# FPGA_MGT.net
KiCad netlist of a schematic drawn in Altium Designer
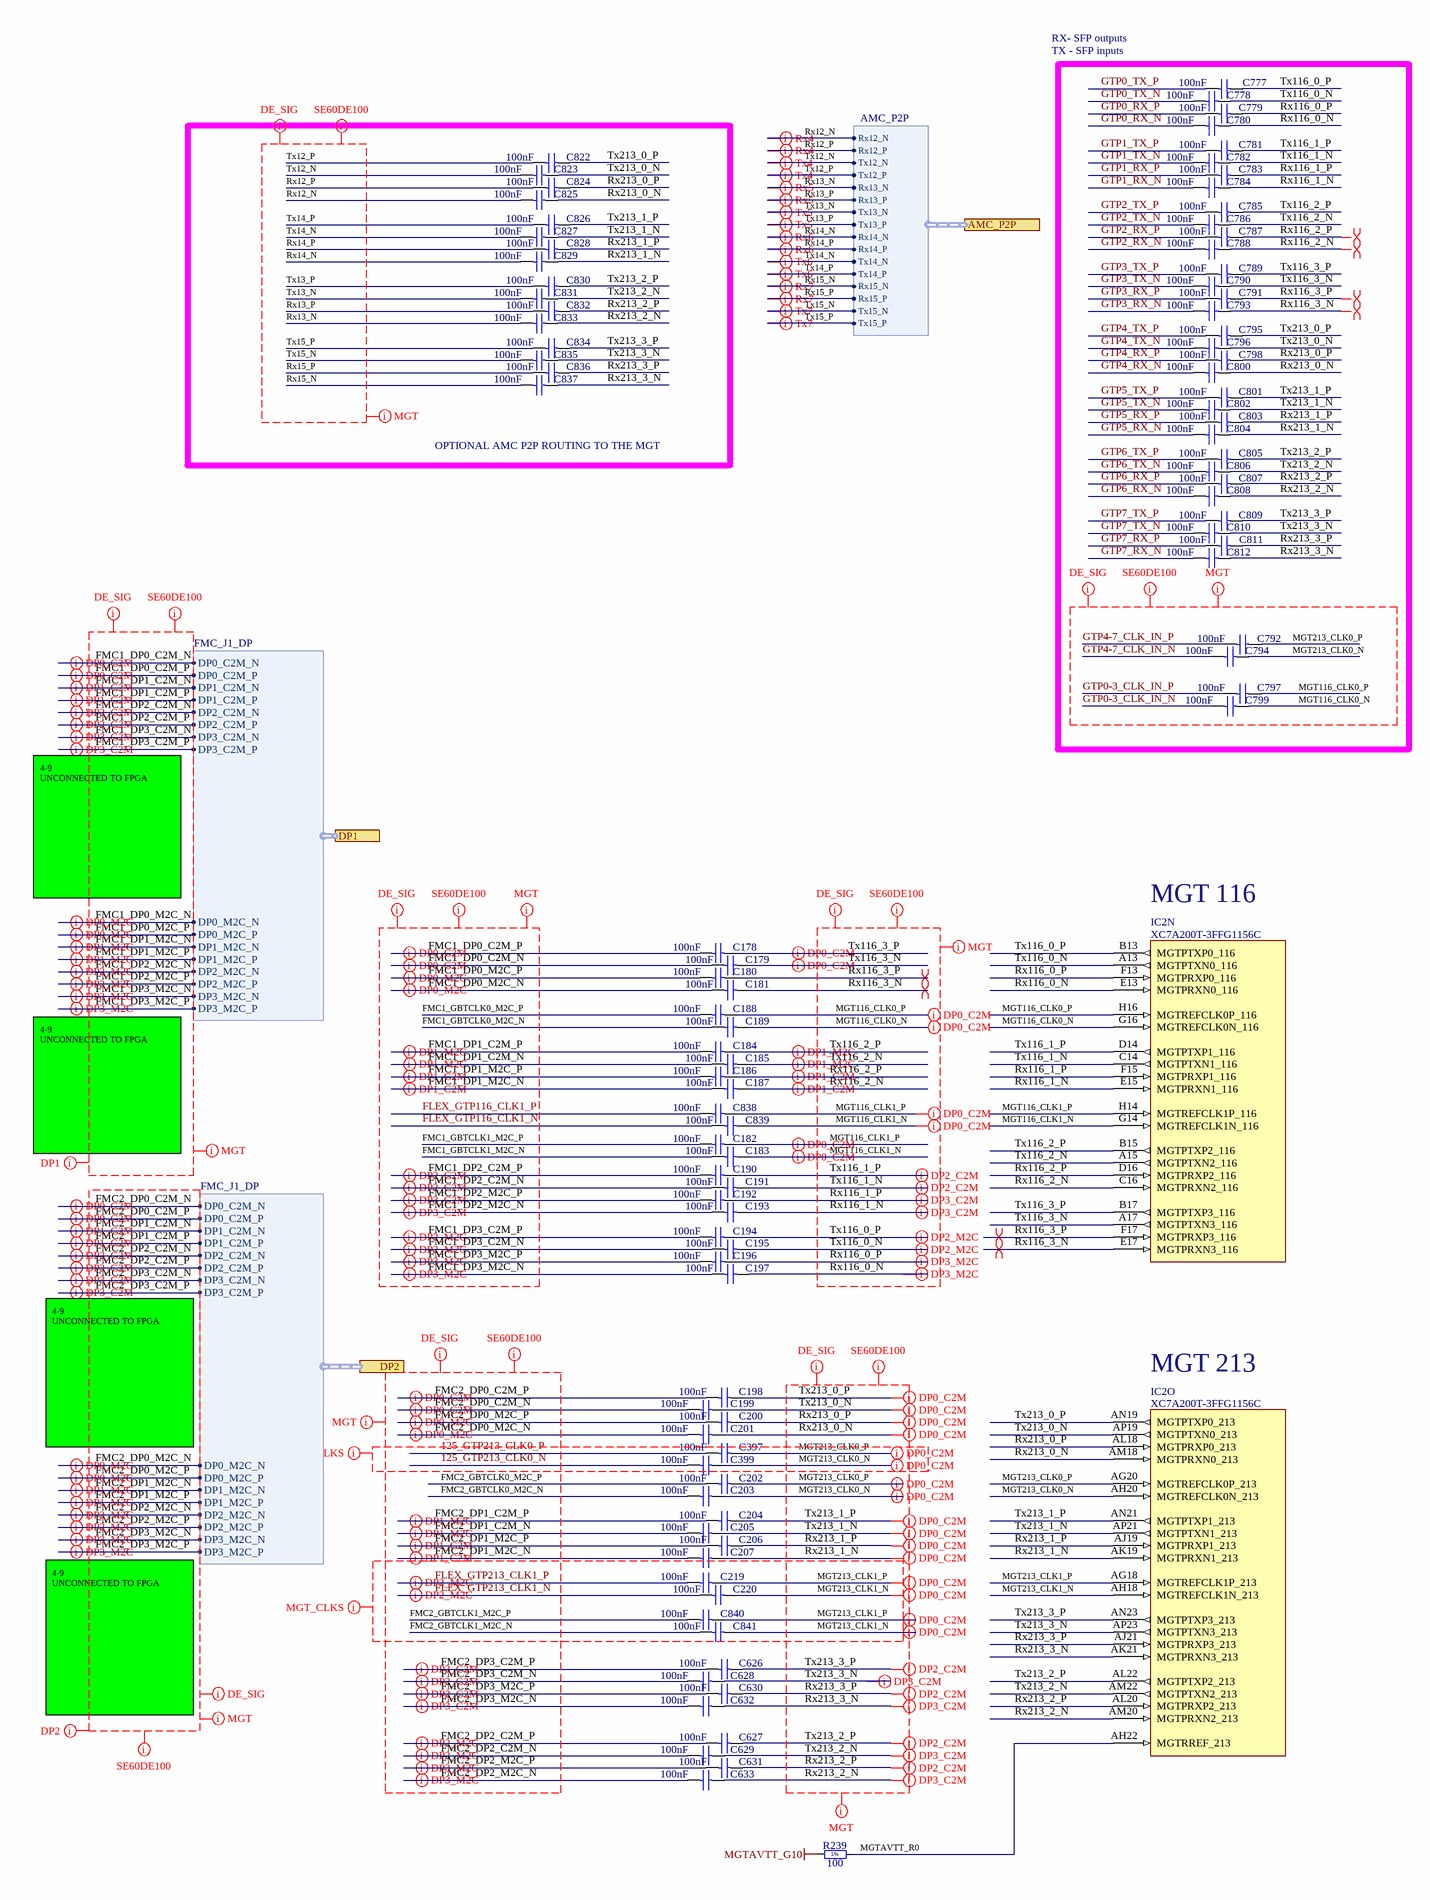
[diagram p0: FPGA_MGT.SchDoc, left]
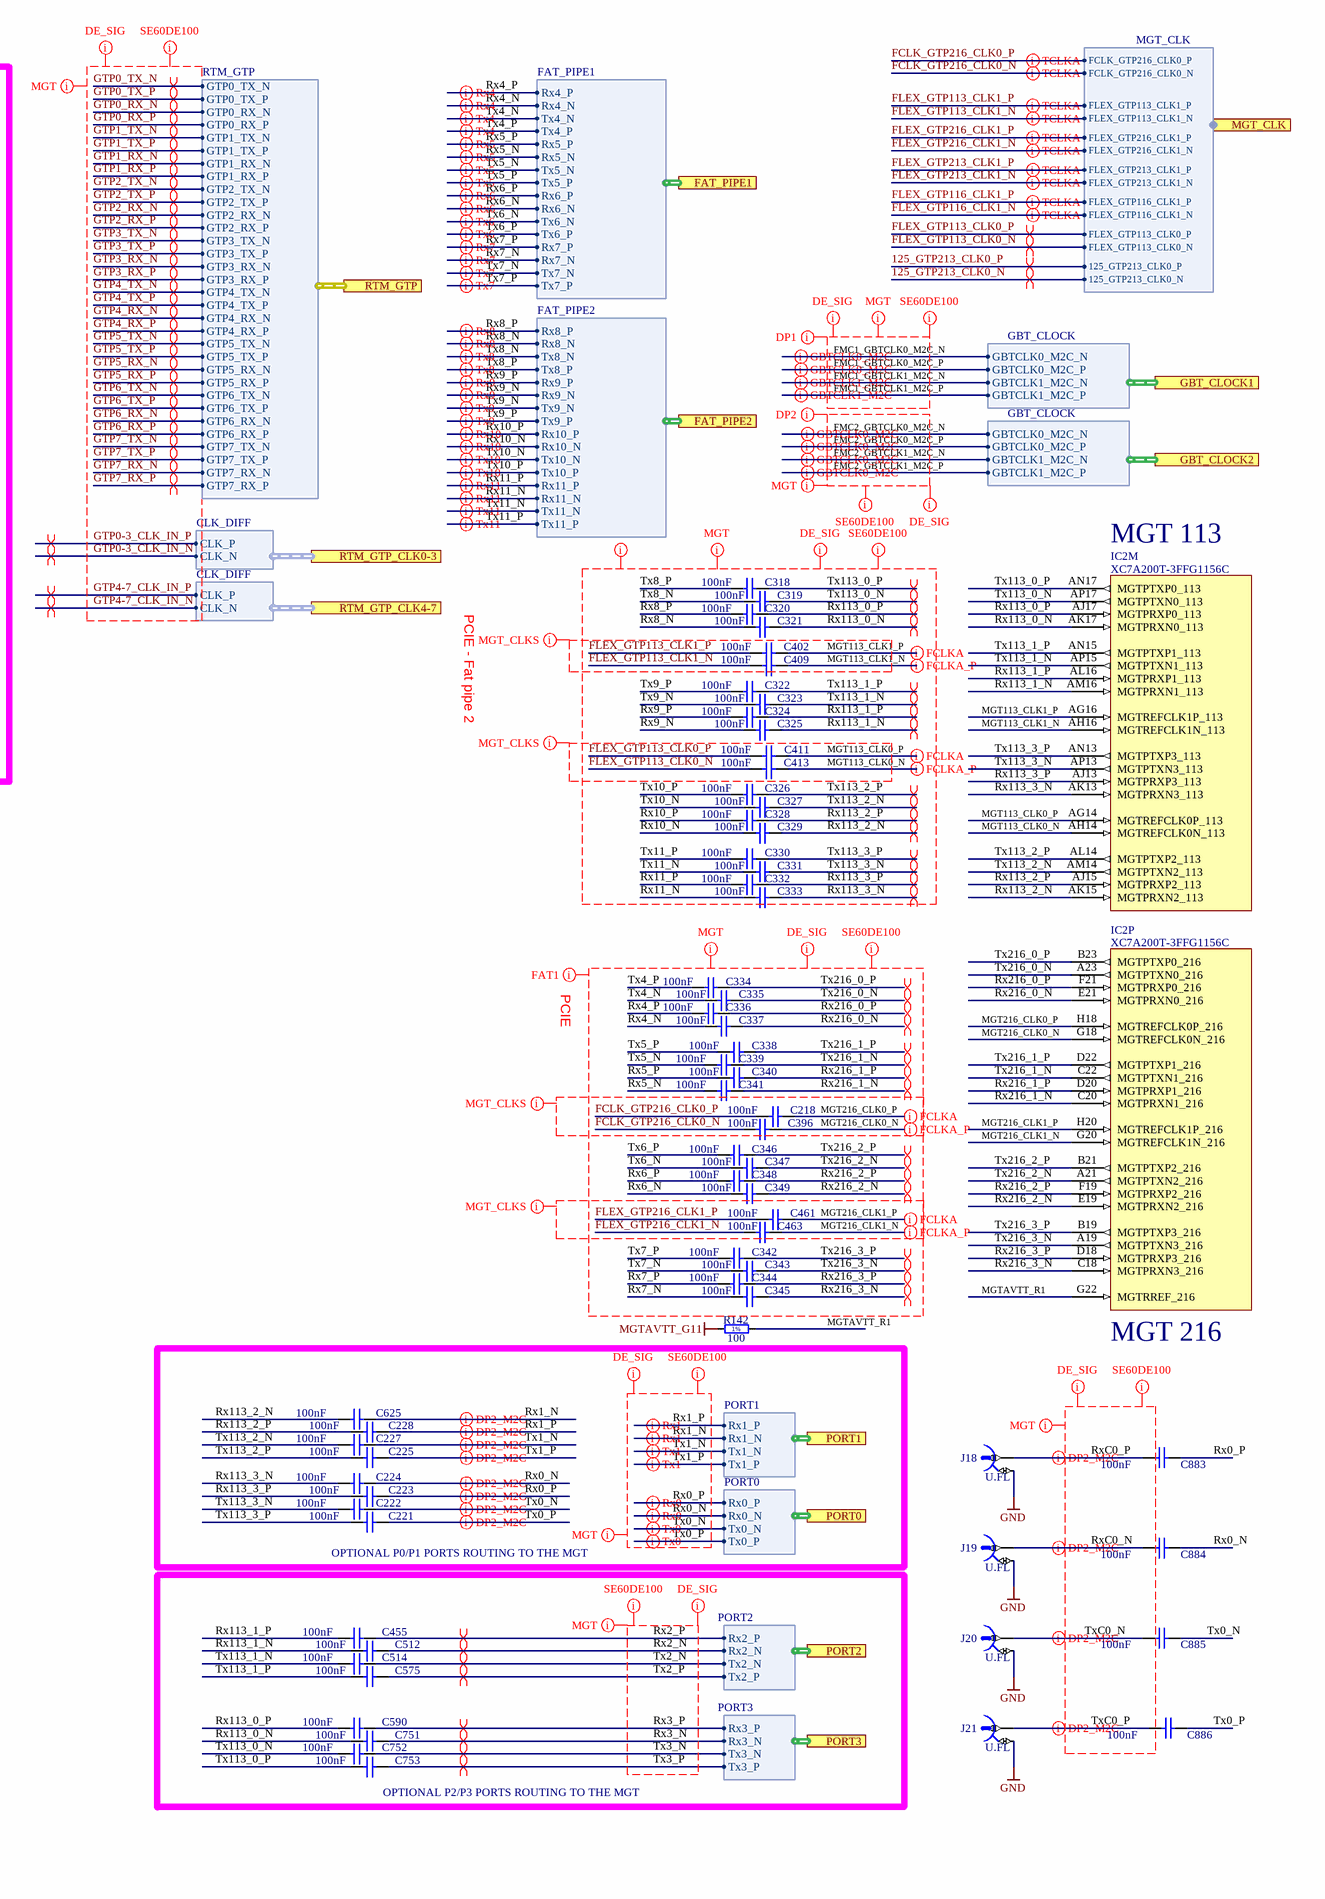
[diagram p1: FPGA_MGT.SchDoc, right]

(export (version "E")
  (design (tool "Eeschema 10.0.6"))
  (components
    (comp (ref "C178")
      (value "100nF")
      (footprint "CAPC0603X33N")
      (description "Non-polarised capacitor")
      (fields
        (field (name "PART NUMBER") "CC0201_100NF_6.3V_10%_X5R")
        (field (name "VOLTAGE") "6.3V")
        (field (name "AUTHOR") "CERN DEM JLC")
      )
      (libsource (lib "Capacitors") (part "Capacitor - non polarized"))
    )
    (comp (ref "C179")
      (value "100nF")
      (footprint "CAPC0603X33N")
      (description "Non-polarised capacitor")
      (fields
        (field (name "PART NUMBER") "CC0201_100NF_6.3V_10%_X5R")
        (field (name "VOLTAGE") "6.3V")
        (field (name "AUTHOR") "CERN DEM JLC")
      )
      (libsource (lib "Capacitors") (part "Capacitor - non polarized"))
    )
    (comp (ref "C180")
      (value "100nF")
      (footprint "CAPC0603X33N")
      (description "Non-polarised capacitor")
      (fields
        (field (name "PART NUMBER") "CC0201_100NF_6.3V_10%_X5R")
        (field (name "VOLTAGE") "6.3V")
        (field (name "AUTHOR") "CERN DEM JLC")
      )
      (libsource (lib "Capacitors") (part "Capacitor - non polarized"))
    )
    (comp (ref "C181")
      (value "100nF")
      (footprint "CAPC0603X33N")
      (description "Non-polarised capacitor")
      (fields
        (field (name "PART NUMBER") "CC0201_100NF_6.3V_10%_X5R")
        (field (name "VOLTAGE") "6.3V")
        (field (name "AUTHOR") "CERN DEM JLC")
      )
      (libsource (lib "Capacitors") (part "Capacitor - non polarized"))
    )
    (comp (ref "C182")
      (value "100nF")
      (footprint "CAPC0603X33N")
      (description "Non-polarised capacitor")
      (fields
        (field (name "PART NUMBER") "CC0201_100NF_6.3V_10%_X5R")
        (field (name "VOLTAGE") "6.3V")
        (field (name "AUTHOR") "CERN DEM JLC")
      )
      (libsource (lib "Capacitors") (part "Capacitor - non polarized"))
    )
    (comp (ref "C183")
      (value "100nF")
      (footprint "CAPC0603X33N")
      (description "Non-polarised capacitor")
      (fields
        (field (name "PART NUMBER") "CC0201_100NF_6.3V_10%_X5R")
        (field (name "VOLTAGE") "6.3V")
        (field (name "AUTHOR") "CERN DEM JLC")
      )
      (libsource (lib "Capacitors") (part "Capacitor - non polarized"))
    )
    (comp (ref "C184")
      (value "100nF")
      (footprint "CAPC0603X33N")
      (description "Non-polarised capacitor")
      (fields
        (field (name "PART NUMBER") "CC0201_100NF_6.3V_10%_X5R")
        (field (name "VOLTAGE") "6.3V")
        (field (name "AUTHOR") "CERN DEM JLC")
      )
      (libsource (lib "Capacitors") (part "Capacitor - non polarized"))
    )
    (comp (ref "C185")
      (value "100nF")
      (footprint "CAPC0603X33N")
      (description "Non-polarised capacitor")
      (fields
        (field (name "PART NUMBER") "CC0201_100NF_6.3V_10%_X5R")
        (field (name "VOLTAGE") "6.3V")
        (field (name "AUTHOR") "CERN DEM JLC")
      )
      (libsource (lib "Capacitors") (part "Capacitor - non polarized"))
    )
    (comp (ref "C186")
      (value "100nF")
      (footprint "CAPC0603X33N")
      (description "Non-polarised capacitor")
      (fields
        (field (name "PART NUMBER") "CC0201_100NF_6.3V_10%_X5R")
        (field (name "VOLTAGE") "6.3V")
        (field (name "AUTHOR") "CERN DEM JLC")
      )
      (libsource (lib "Capacitors") (part "Capacitor - non polarized"))
    )
    (comp (ref "C187")
      (value "100nF")
      (footprint "CAPC0603X33N")
      (description "Non-polarised capacitor")
      (fields
        (field (name "PART NUMBER") "CC0201_100NF_6.3V_10%_X5R")
        (field (name "VOLTAGE") "6.3V")
        (field (name "AUTHOR") "CERN DEM JLC")
      )
      (libsource (lib "Capacitors") (part "Capacitor - non polarized"))
    )
    (comp (ref "C188")
      (value "100nF")
      (footprint "CAPC0603X33N")
      (description "Non-polarised capacitor")
      (fields
        (field (name "PART NUMBER") "CC0201_100NF_6.3V_10%_X5R")
        (field (name "VOLTAGE") "6.3V")
        (field (name "AUTHOR") "CERN DEM JLC")
      )
      (libsource (lib "Capacitors") (part "Capacitor - non polarized"))
    )
    (comp (ref "C189")
      (value "100nF")
      (footprint "CAPC0603X33N")
      (description "Non-polarised capacitor")
      (fields
        (field (name "PART NUMBER") "CC0201_100NF_6.3V_10%_X5R")
        (field (name "VOLTAGE") "6.3V")
        (field (name "AUTHOR") "CERN DEM JLC")
      )
      (libsource (lib "Capacitors") (part "Capacitor - non polarized"))
    )
    (comp (ref "C190")
      (value "100nF")
      (footprint "CAPC0603X33N")
      (description "Non-polarised capacitor")
      (fields
        (field (name "PART NUMBER") "CC0201_100NF_6.3V_10%_X5R")
        (field (name "VOLTAGE") "6.3V")
        (field (name "AUTHOR") "CERN DEM JLC")
      )
      (libsource (lib "Capacitors") (part "Capacitor - non polarized"))
    )
    (comp (ref "C191")
      (value "100nF")
      (footprint "CAPC0603X33N")
      (description "Non-polarised capacitor")
      (fields
        (field (name "PART NUMBER") "CC0201_100NF_6.3V_10%_X5R")
        (field (name "VOLTAGE") "6.3V")
        (field (name "AUTHOR") "CERN DEM JLC")
      )
      (libsource (lib "Capacitors") (part "Capacitor - non polarized"))
    )
    (comp (ref "C192")
      (value "100nF")
      (footprint "CAPC0603X33N")
      (description "Non-polarised capacitor")
      (fields
        (field (name "PART NUMBER") "CC0201_100NF_6.3V_10%_X5R")
        (field (name "VOLTAGE") "6.3V")
        (field (name "AUTHOR") "CERN DEM JLC")
      )
      (libsource (lib "Capacitors") (part "Capacitor - non polarized"))
    )
    (comp (ref "C193")
      (value "100nF")
      (footprint "CAPC0603X33N")
      (description "Non-polarised capacitor")
      (fields
        (field (name "PART NUMBER") "CC0201_100NF_6.3V_10%_X5R")
        (field (name "VOLTAGE") "6.3V")
        (field (name "AUTHOR") "CERN DEM JLC")
      )
      (libsource (lib "Capacitors") (part "Capacitor - non polarized"))
    )
    (comp (ref "C194")
      (value "100nF")
      (footprint "CAPC0603X33N")
      (description "Non-polarised capacitor")
      (fields
        (field (name "PART NUMBER") "CC0201_100NF_6.3V_10%_X5R")
        (field (name "VOLTAGE") "6.3V")
        (field (name "AUTHOR") "CERN DEM JLC")
      )
      (libsource (lib "Capacitors") (part "Capacitor - non polarized"))
    )
    (comp (ref "C195")
      (value "100nF")
      (footprint "CAPC0603X33N")
      (description "Non-polarised capacitor")
      (fields
        (field (name "PART NUMBER") "CC0201_100NF_6.3V_10%_X5R")
        (field (name "VOLTAGE") "6.3V")
        (field (name "AUTHOR") "CERN DEM JLC")
      )
      (libsource (lib "Capacitors") (part "Capacitor - non polarized"))
    )
    (comp (ref "C196")
      (value "100nF")
      (footprint "CAPC0603X33N")
      (description "Non-polarised capacitor")
      (fields
        (field (name "PART NUMBER") "CC0201_100NF_6.3V_10%_X5R")
        (field (name "VOLTAGE") "6.3V")
        (field (name "AUTHOR") "CERN DEM JLC")
      )
      (libsource (lib "Capacitors") (part "Capacitor - non polarized"))
    )
    (comp (ref "C197")
      (value "100nF")
      (footprint "CAPC0603X33N")
      (description "Non-polarised capacitor")
      (fields
        (field (name "PART NUMBER") "CC0201_100NF_6.3V_10%_X5R")
        (field (name "VOLTAGE") "6.3V")
        (field (name "AUTHOR") "CERN DEM JLC")
      )
      (libsource (lib "Capacitors") (part "Capacitor - non polarized"))
    )
    (comp (ref "C198")
      (value "100nF")
      (footprint "CAPC0603X33N")
      (description "Non-polarised capacitor")
      (fields
        (field (name "PART NUMBER") "CC0201_100NF_6.3V_10%_X5R")
        (field (name "VOLTAGE") "6.3V")
        (field (name "AUTHOR") "CERN DEM JLC")
      )
      (libsource (lib "Capacitors") (part "Capacitor - non polarized"))
    )
    (comp (ref "C199")
      (value "100nF")
      (footprint "CAPC0603X33N")
      (description "Non-polarised capacitor")
      (fields
        (field (name "PART NUMBER") "CC0201_100NF_6.3V_10%_X5R")
        (field (name "VOLTAGE") "6.3V")
        (field (name "AUTHOR") "CERN DEM JLC")
      )
      (libsource (lib "Capacitors") (part "Capacitor - non polarized"))
    )
    (comp (ref "C200")
      (value "100nF")
      (footprint "CAPC0603X33N")
      (description "Non-polarised capacitor")
      (fields
        (field (name "PART NUMBER") "CC0201_100NF_6.3V_10%_X5R")
        (field (name "VOLTAGE") "6.3V")
        (field (name "AUTHOR") "CERN DEM JLC")
      )
      (libsource (lib "Capacitors") (part "Capacitor - non polarized"))
    )
    (comp (ref "C201")
      (value "100nF")
      (footprint "CAPC0603X33N")
      (description "Non-polarised capacitor")
      (fields
        (field (name "PART NUMBER") "CC0201_100NF_6.3V_10%_X5R")
        (field (name "VOLTAGE") "6.3V")
        (field (name "AUTHOR") "CERN DEM JLC")
      )
      (libsource (lib "Capacitors") (part "Capacitor - non polarized"))
    )
    (comp (ref "C202")
      (value "100nF")
      (footprint "CAPC0603X33N")
      (description "Non-polarised capacitor")
      (fields
        (field (name "PART NUMBER") "CC0201_100NF_6.3V_10%_X5R")
        (field (name "VOLTAGE") "6.3V")
        (field (name "AUTHOR") "CERN DEM JLC")
      )
      (libsource (lib "Capacitors") (part "Capacitor - non polarized"))
    )
    (comp (ref "C203")
      (value "100nF")
      (footprint "CAPC0603X33N")
      (description "Non-polarised capacitor")
      (fields
        (field (name "PART NUMBER") "CC0201_100NF_6.3V_10%_X5R")
        (field (name "VOLTAGE") "6.3V")
        (field (name "AUTHOR") "CERN DEM JLC")
      )
      (libsource (lib "Capacitors") (part "Capacitor - non polarized"))
    )
    (comp (ref "C204")
      (value "100nF")
      (footprint "CAPC0603X33N")
      (description "Non-polarised capacitor")
      (fields
        (field (name "PART NUMBER") "CC0201_100NF_6.3V_10%_X5R")
        (field (name "VOLTAGE") "6.3V")
        (field (name "AUTHOR") "CERN DEM JLC")
      )
      (libsource (lib "Capacitors") (part "Capacitor - non polarized"))
    )
    (comp (ref "C205")
      (value "100nF")
      (footprint "CAPC0603X33N")
      (description "Non-polarised capacitor")
      (fields
        (field (name "PART NUMBER") "CC0201_100NF_6.3V_10%_X5R")
        (field (name "VOLTAGE") "6.3V")
        (field (name "AUTHOR") "CERN DEM JLC")
      )
      (libsource (lib "Capacitors") (part "Capacitor - non polarized"))
    )
    (comp (ref "C206")
      (value "100nF")
      (footprint "CAPC0603X33N")
      (description "Non-polarised capacitor")
      (fields
        (field (name "PART NUMBER") "CC0201_100NF_6.3V_10%_X5R")
        (field (name "VOLTAGE") "6.3V")
        (field (name "AUTHOR") "CERN DEM JLC")
      )
      (libsource (lib "Capacitors") (part "Capacitor - non polarized"))
    )
    (comp (ref "C207")
      (value "100nF")
      (footprint "CAPC0603X33N")
      (description "Non-polarised capacitor")
      (fields
        (field (name "PART NUMBER") "CC0201_100NF_6.3V_10%_X5R")
        (field (name "VOLTAGE") "6.3V")
        (field (name "AUTHOR") "CERN DEM JLC")
      )
      (libsource (lib "Capacitors") (part "Capacitor - non polarized"))
    )
    (comp (ref "C218")
      (value "100nF")
      (footprint "CAPC0603X33N")
      (description "Non-polarised capacitor")
      (fields
        (field (name "PART NUMBER") "CC0201_100NF_6.3V_10%_X5R")
        (field (name "VOLTAGE") "6.3V")
        (field (name "AUTHOR") "CERN DEM JLC")
      )
      (libsource (lib "Capacitors") (part "Capacitor - non polarized"))
    )
    (comp (ref "C219")
      (value "100nF")
      (footprint "CAPC0603X33N")
      (description "Non-polarised capacitor")
      (fields
        (field (name "PART NUMBER") "CC0201_100NF_6.3V_10%_X5R")
        (field (name "VOLTAGE") "6.3V")
        (field (name "AUTHOR") "CERN DEM JLC")
      )
      (libsource (lib "Capacitors") (part "Capacitor - non polarized"))
    )
    (comp (ref "C220")
      (value "100nF")
      (footprint "CAPC0603X33N")
      (description "Non-polarised capacitor")
      (fields
        (field (name "PART NUMBER") "CC0201_100NF_6.3V_10%_X5R")
        (field (name "VOLTAGE") "6.3V")
        (field (name "AUTHOR") "CERN DEM JLC")
      )
      (libsource (lib "Capacitors") (part "Capacitor - non polarized"))
    )
    (comp (ref "C221")
      (value "100nF")
      (footprint "CAPC0603X33N")
      (description "Non-polarised capacitor")
      (fields
        (field (name "PART NUMBER") "CC0201_100NF_6.3V_10%_X5R")
        (field (name "VOLTAGE") "6.3V")
        (field (name "AUTHOR") "CERN DEM JLC")
      )
      (libsource (lib "Capacitors") (part "Capacitor - non polarized"))
    )
    (comp (ref "C222")
      (value "100nF")
      (footprint "CAPC0603X33N")
      (description "Non-polarised capacitor")
      (fields
        (field (name "PART NUMBER") "CC0201_100NF_6.3V_10%_X5R")
        (field (name "VOLTAGE") "6.3V")
        (field (name "AUTHOR") "CERN DEM JLC")
      )
      (libsource (lib "Capacitors") (part "Capacitor - non polarized"))
    )
    (comp (ref "C223")
      (value "100nF")
      (footprint "CAPC0603X33N")
      (description "Non-polarised capacitor")
      (fields
        (field (name "PART NUMBER") "CC0201_100NF_6.3V_10%_X5R")
        (field (name "VOLTAGE") "6.3V")
        (field (name "AUTHOR") "CERN DEM JLC")
      )
      (libsource (lib "Capacitors") (part "Capacitor - non polarized"))
    )
    (comp (ref "C224")
      (value "100nF")
      (footprint "CAPC0603X33N")
      (description "Non-polarised capacitor")
      (fields
        (field (name "PART NUMBER") "CC0201_100NF_6.3V_10%_X5R")
        (field (name "VOLTAGE") "6.3V")
        (field (name "AUTHOR") "CERN DEM JLC")
      )
      (libsource (lib "Capacitors") (part "Capacitor - non polarized"))
    )
    (comp (ref "C225")
      (value "100nF")
      (footprint "CAPC0603X33N")
      (description "Non-polarised capacitor")
      (fields
        (field (name "PART NUMBER") "CC0201_100NF_6.3V_10%_X5R")
        (field (name "VOLTAGE") "6.3V")
        (field (name "AUTHOR") "CERN DEM JLC")
      )
      (libsource (lib "Capacitors") (part "Capacitor - non polarized"))
    )
    (comp (ref "C227")
      (value "100nF")
      (footprint "CAPC0603X33N")
      (description "Non-polarised capacitor")
      (fields
        (field (name "PART NUMBER") "CC0201_100NF_6.3V_10%_X5R")
        (field (name "VOLTAGE") "6.3V")
        (field (name "AUTHOR") "CERN DEM JLC")
      )
      (libsource (lib "Capacitors") (part "Capacitor - non polarized"))
    )
    (comp (ref "C228")
      (value "100nF")
      (footprint "CAPC0603X33N")
      (description "Non-polarised capacitor")
      (fields
        (field (name "PART NUMBER") "CC0201_100NF_6.3V_10%_X5R")
        (field (name "VOLTAGE") "6.3V")
        (field (name "AUTHOR") "CERN DEM JLC")
      )
      (libsource (lib "Capacitors") (part "Capacitor - non polarized"))
    )
    (comp (ref "C318")
      (value "100nF")
      (footprint "CAPC0603X33N")
      (description "Non-polarised capacitor")
      (fields
        (field (name "PART NUMBER") "CC0201_100NF_6.3V_10%_X5R")
        (field (name "VOLTAGE") "6.3V")
        (field (name "AUTHOR") "CERN DEM JLC")
      )
      (libsource (lib "Capacitors") (part "Capacitor - non polarized"))
    )
    (comp (ref "C319")
      (value "100nF")
      (footprint "CAPC0603X33N")
      (description "Non-polarised capacitor")
      (fields
        (field (name "PART NUMBER") "CC0201_100NF_6.3V_10%_X5R")
        (field (name "VOLTAGE") "6.3V")
        (field (name "AUTHOR") "CERN DEM JLC")
      )
      (libsource (lib "Capacitors") (part "Capacitor - non polarized"))
    )
    (comp (ref "C320")
      (value "100nF")
      (footprint "CAPC0603X33N")
      (description "Non-polarised capacitor")
      (fields
        (field (name "PART NUMBER") "CC0201_100NF_6.3V_10%_X5R")
        (field (name "VOLTAGE") "6.3V")
        (field (name "AUTHOR") "CERN DEM JLC")
      )
      (libsource (lib "Capacitors") (part "Capacitor - non polarized"))
    )
    (comp (ref "C321")
      (value "100nF")
      (footprint "CAPC0603X33N")
      (description "Non-polarised capacitor")
      (fields
        (field (name "PART NUMBER") "CC0201_100NF_6.3V_10%_X5R")
        (field (name "VOLTAGE") "6.3V")
        (field (name "AUTHOR") "CERN DEM JLC")
      )
      (libsource (lib "Capacitors") (part "Capacitor - non polarized"))
    )
    (comp (ref "C322")
      (value "100nF")
      (footprint "CAPC0603X33N")
      (description "Non-polarised capacitor")
      (fields
        (field (name "PART NUMBER") "CC0201_100NF_6.3V_10%_X5R")
        (field (name "VOLTAGE") "6.3V")
        (field (name "AUTHOR") "CERN DEM JLC")
      )
      (libsource (lib "Capacitors") (part "Capacitor - non polarized"))
    )
    (comp (ref "C323")
      (value "100nF")
      (footprint "CAPC0603X33N")
      (description "Non-polarised capacitor")
      (fields
        (field (name "PART NUMBER") "CC0201_100NF_6.3V_10%_X5R")
        (field (name "VOLTAGE") "6.3V")
        (field (name "AUTHOR") "CERN DEM JLC")
      )
      (libsource (lib "Capacitors") (part "Capacitor - non polarized"))
    )
    (comp (ref "C324")
      (value "100nF")
      (footprint "CAPC0603X33N")
      (description "Non-polarised capacitor")
      (fields
        (field (name "PART NUMBER") "CC0201_100NF_6.3V_10%_X5R")
        (field (name "VOLTAGE") "6.3V")
        (field (name "AUTHOR") "CERN DEM JLC")
      )
      (libsource (lib "Capacitors") (part "Capacitor - non polarized"))
    )
    (comp (ref "C325")
      (value "100nF")
      (footprint "CAPC0603X33N")
      (description "Non-polarised capacitor")
      (fields
        (field (name "PART NUMBER") "CC0201_100NF_6.3V_10%_X5R")
        (field (name "VOLTAGE") "6.3V")
        (field (name "AUTHOR") "CERN DEM JLC")
      )
      (libsource (lib "Capacitors") (part "Capacitor - non polarized"))
    )
    (comp (ref "C326")
      (value "100nF")
      (footprint "CAPC0603X33N")
      (description "Non-polarised capacitor")
      (fields
        (field (name "PART NUMBER") "CC0201_100NF_6.3V_10%_X5R")
        (field (name "VOLTAGE") "6.3V")
        (field (name "AUTHOR") "CERN DEM JLC")
      )
      (libsource (lib "Capacitors") (part "Capacitor - non polarized"))
    )
    (comp (ref "C327")
      (value "100nF")
      (footprint "CAPC0603X33N")
      (description "Non-polarised capacitor")
      (fields
        (field (name "PART NUMBER") "CC0201_100NF_6.3V_10%_X5R")
        (field (name "VOLTAGE") "6.3V")
        (field (name "AUTHOR") "CERN DEM JLC")
      )
      (libsource (lib "Capacitors") (part "Capacitor - non polarized"))
    )
    (comp (ref "C328")
      (value "100nF")
      (footprint "CAPC0603X33N")
      (description "Non-polarised capacitor")
      (fields
        (field (name "PART NUMBER") "CC0201_100NF_6.3V_10%_X5R")
        (field (name "VOLTAGE") "6.3V")
        (field (name "AUTHOR") "CERN DEM JLC")
      )
      (libsource (lib "Capacitors") (part "Capacitor - non polarized"))
    )
    (comp (ref "C329")
      (value "100nF")
      (footprint "CAPC0603X33N")
      (description "Non-polarised capacitor")
      (fields
        (field (name "PART NUMBER") "CC0201_100NF_6.3V_10%_X5R")
        (field (name "VOLTAGE") "6.3V")
        (field (name "AUTHOR") "CERN DEM JLC")
      )
      (libsource (lib "Capacitors") (part "Capacitor - non polarized"))
    )
    (comp (ref "C330")
      (value "100nF")
      (footprint "CAPC0603X33N")
      (description "Non-polarised capacitor")
      (fields
        (field (name "PART NUMBER") "CC0201_100NF_6.3V_10%_X5R")
        (field (name "VOLTAGE") "6.3V")
        (field (name "AUTHOR") "CERN DEM JLC")
      )
      (libsource (lib "Capacitors") (part "Capacitor - non polarized"))
    )
    (comp (ref "C331")
      (value "100nF")
      (footprint "CAPC0603X33N")
      (description "Non-polarised capacitor")
      (fields
        (field (name "PART NUMBER") "CC0201_100NF_6.3V_10%_X5R")
        (field (name "VOLTAGE") "6.3V")
        (field (name "AUTHOR") "CERN DEM JLC")
      )
      (libsource (lib "Capacitors") (part "Capacitor - non polarized"))
    )
    (comp (ref "C332")
      (value "100nF")
      (footprint "CAPC0603X33N")
      (description "Non-polarised capacitor")
      (fields
        (field (name "PART NUMBER") "CC0201_100NF_6.3V_10%_X5R")
        (field (name "VOLTAGE") "6.3V")
        (field (name "AUTHOR") "CERN DEM JLC")
      )
      (libsource (lib "Capacitors") (part "Capacitor - non polarized"))
    )
    (comp (ref "C333")
      (value "100nF")
      (footprint "CAPC0603X33N")
      (description "Non-polarised capacitor")
      (fields
        (field (name "PART NUMBER") "CC0201_100NF_6.3V_10%_X5R")
        (field (name "VOLTAGE") "6.3V")
        (field (name "AUTHOR") "CERN DEM JLC")
      )
      (libsource (lib "Capacitors") (part "Capacitor - non polarized"))
    )
    (comp (ref "C334")
      (value "100nF")
      (footprint "CAPC0603X33N")
      (description "Non-polarised capacitor")
      (fields
        (field (name "PART NUMBER") "CC0201_100NF_6.3V_10%_X5R")
        (field (name "VOLTAGE") "6.3V")
        (field (name "AUTHOR") "CERN DEM JLC")
      )
      (libsource (lib "Capacitors") (part "Capacitor - non polarized"))
    )
    (comp (ref "C335")
      (value "100nF")
      (footprint "CAPC0603X33N")
      (description "Non-polarised capacitor")
      (fields
        (field (name "PART NUMBER") "CC0201_100NF_6.3V_10%_X5R")
        (field (name "VOLTAGE") "6.3V")
        (field (name "AUTHOR") "CERN DEM JLC")
      )
      (libsource (lib "Capacitors") (part "Capacitor - non polarized"))
    )
    (comp (ref "C336")
      (value "100nF")
      (footprint "CAPC0603X33N")
      (description "Non-polarised capacitor")
      (fields
        (field (name "PART NUMBER") "CC0201_100NF_6.3V_10%_X5R")
        (field (name "VOLTAGE") "6.3V")
        (field (name "AUTHOR") "CERN DEM JLC")
      )
      (libsource (lib "Capacitors") (part "Capacitor - non polarized"))
    )
    (comp (ref "C337")
      (value "100nF")
      (footprint "CAPC0603X33N")
      (description "Non-polarised capacitor")
      (fields
        (field (name "PART NUMBER") "CC0201_100NF_6.3V_10%_X5R")
        (field (name "VOLTAGE") "6.3V")
        (field (name "AUTHOR") "CERN DEM JLC")
      )
      (libsource (lib "Capacitors") (part "Capacitor - non polarized"))
    )
    (comp (ref "C338")
      (value "100nF")
      (footprint "CAPC0603X33N")
      (description "Non-polarised capacitor")
      (fields
        (field (name "PART NUMBER") "CC0201_100NF_6.3V_10%_X5R")
        (field (name "VOLTAGE") "6.3V")
        (field (name "AUTHOR") "CERN DEM JLC")
      )
      (libsource (lib "Capacitors") (part "Capacitor - non polarized"))
    )
    (comp (ref "C339")
      (value "100nF")
      (footprint "CAPC0603X33N")
      (description "Non-polarised capacitor")
      (fields
        (field (name "PART NUMBER") "CC0201_100NF_6.3V_10%_X5R")
        (field (name "VOLTAGE") "6.3V")
        (field (name "AUTHOR") "CERN DEM JLC")
      )
      (libsource (lib "Capacitors") (part "Capacitor - non polarized"))
    )
    (comp (ref "C340")
      (value "100nF")
      (footprint "CAPC0603X33N")
      (description "Non-polarised capacitor")
      (fields
        (field (name "PART NUMBER") "CC0201_100NF_6.3V_10%_X5R")
        (field (name "VOLTAGE") "6.3V")
        (field (name "AUTHOR") "CERN DEM JLC")
      )
      (libsource (lib "Capacitors") (part "Capacitor - non polarized"))
    )
    (comp (ref "C341")
      (value "100nF")
      (footprint "CAPC0603X33N")
      (description "Non-polarised capacitor")
      (fields
        (field (name "PART NUMBER") "CC0201_100NF_6.3V_10%_X5R")
        (field (name "VOLTAGE") "6.3V")
        (field (name "AUTHOR") "CERN DEM JLC")
      )
      (libsource (lib "Capacitors") (part "Capacitor - non polarized"))
    )
    (comp (ref "C342")
      (value "100nF")
      (footprint "CAPC0603X33N")
      (description "Non-polarised capacitor")
      (fields
        (field (name "PART NUMBER") "CC0201_100NF_6.3V_10%_X5R")
        (field (name "VOLTAGE") "6.3V")
        (field (name "AUTHOR") "CERN DEM JLC")
      )
      (libsource (lib "Capacitors") (part "Capacitor - non polarized"))
    )
    (comp (ref "C343")
      (value "100nF")
      (footprint "CAPC0603X33N")
      (description "Non-polarised capacitor")
      (fields
        (field (name "PART NUMBER") "CC0201_100NF_6.3V_10%_X5R")
        (field (name "VOLTAGE") "6.3V")
        (field (name "AUTHOR") "CERN DEM JLC")
      )
      (libsource (lib "Capacitors") (part "Capacitor - non polarized"))
    )
    (comp (ref "C344")
      (value "100nF")
      (footprint "CAPC0603X33N")
      (description "Non-polarised capacitor")
      (fields
        (field (name "PART NUMBER") "CC0201_100NF_6.3V_10%_X5R")
        (field (name "VOLTAGE") "6.3V")
        (field (name "AUTHOR") "CERN DEM JLC")
      )
      (libsource (lib "Capacitors") (part "Capacitor - non polarized"))
    )
    (comp (ref "C345")
      (value "100nF")
      (footprint "CAPC0603X33N")
      (description "Non-polarised capacitor")
      (fields
        (field (name "PART NUMBER") "CC0201_100NF_6.3V_10%_X5R")
        (field (name "VOLTAGE") "6.3V")
        (field (name "AUTHOR") "CERN DEM JLC")
      )
      (libsource (lib "Capacitors") (part "Capacitor - non polarized"))
    )
    (comp (ref "C346")
      (value "100nF")
      (footprint "CAPC0603X33N")
      (description "Non-polarised capacitor")
      (fields
        (field (name "PART NUMBER") "CC0201_100NF_6.3V_10%_X5R")
        (field (name "VOLTAGE") "6.3V")
        (field (name "AUTHOR") "CERN DEM JLC")
      )
      (libsource (lib "Capacitors") (part "Capacitor - non polarized"))
    )
    (comp (ref "C347")
      (value "100nF")
      (footprint "CAPC0603X33N")
      (description "Non-polarised capacitor")
      (fields
        (field (name "PART NUMBER") "CC0201_100NF_6.3V_10%_X5R")
        (field (name "VOLTAGE") "6.3V")
        (field (name "AUTHOR") "CERN DEM JLC")
      )
      (libsource (lib "Capacitors") (part "Capacitor - non polarized"))
    )
    (comp (ref "C348")
      (value "100nF")
      (footprint "CAPC0603X33N")
      (description "Non-polarised capacitor")
      (fields
        (field (name "PART NUMBER") "CC0201_100NF_6.3V_10%_X5R")
        (field (name "VOLTAGE") "6.3V")
        (field (name "AUTHOR") "CERN DEM JLC")
      )
      (libsource (lib "Capacitors") (part "Capacitor - non polarized"))
    )
    (comp (ref "C349")
      (value "100nF")
      (footprint "CAPC0603X33N")
      (description "Non-polarised capacitor")
      (fields
        (field (name "PART NUMBER") "CC0201_100NF_6.3V_10%_X5R")
        (field (name "VOLTAGE") "6.3V")
        (field (name "AUTHOR") "CERN DEM JLC")
      )
      (libsource (lib "Capacitors") (part "Capacitor - non polarized"))
    )
    (comp (ref "C396")
      (value "100nF")
      (footprint "CAPC0603X33N")
      (description "Non-polarised capacitor")
      (fields
        (field (name "PART NUMBER") "CC0201_100NF_6.3V_10%_X5R")
        (field (name "VOLTAGE") "6.3V")
        (field (name "AUTHOR") "CERN DEM JLC")
      )
      (libsource (lib "Capacitors") (part "Capacitor - non polarized"))
    )
    (comp (ref "C397")
      (value "100nF")
      (footprint "CAPC0603X33N")
      (description "Non-polarised capacitor")
      (fields
        (field (name "PART NUMBER") "CC0201_100NF_6.3V_10%_X5R")
        (field (name "VOLTAGE") "6.3V")
        (field (name "AUTHOR") "CERN DEM JLC")
      )
      (libsource (lib "Capacitors") (part "Capacitor - non polarized"))
    )
    (comp (ref "C399")
      (value "100nF")
      (footprint "CAPC0603X33N")
      (description "Non-polarised capacitor")
      (fields
        (field (name "PART NUMBER") "CC0201_100NF_6.3V_10%_X5R")
        (field (name "VOLTAGE") "6.3V")
        (field (name "AUTHOR") "CERN DEM JLC")
      )
      (libsource (lib "Capacitors") (part "Capacitor - non polarized"))
    )
    (comp (ref "C402")
      (value "100nF")
      (footprint "CAPC0603X33N")
      (description "Non-polarised capacitor")
      (fields
        (field (name "PART NUMBER") "CC0201_100NF_6.3V_10%_X5R")
        (field (name "VOLTAGE") "6.3V")
        (field (name "AUTHOR") "CERN DEM JLC")
      )
      (libsource (lib "Capacitors") (part "Capacitor - non polarized"))
    )
    (comp (ref "C409")
      (value "100nF")
      (footprint "CAPC0603X33N")
      (description "Non-polarised capacitor")
      (fields
        (field (name "PART NUMBER") "CC0201_100NF_6.3V_10%_X5R")
        (field (name "VOLTAGE") "6.3V")
        (field (name "AUTHOR") "CERN DEM JLC")
      )
      (libsource (lib "Capacitors") (part "Capacitor - non polarized"))
    )
    (comp (ref "C411")
      (value "100nF")
      (footprint "CAPC0603X33N")
      (description "Non-polarised capacitor")
      (fields
        (field (name "PART NUMBER") "CC0201_100NF_6.3V_10%_X5R")
        (field (name "VOLTAGE") "6.3V")
        (field (name "AUTHOR") "CERN DEM JLC")
      )
      (libsource (lib "Capacitors") (part "Capacitor - non polarized"))
    )
    (comp (ref "C413")
      (value "100nF")
      (footprint "CAPC0603X33N")
      (description "Non-polarised capacitor")
      (fields
        (field (name "PART NUMBER") "CC0201_100NF_6.3V_10%_X5R")
        (field (name "VOLTAGE") "6.3V")
        (field (name "AUTHOR") "CERN DEM JLC")
      )
      (libsource (lib "Capacitors") (part "Capacitor - non polarized"))
    )
    (comp (ref "C455")
      (value "100nF")
      (footprint "CAPC0603X33N")
      (description "Non-polarised capacitor")
      (fields
        (field (name "PART NUMBER") "CC0201_100NF_6.3V_10%_X5R")
        (field (name "VOLTAGE") "6.3V")
        (field (name "AUTHOR") "CERN DEM JLC")
      )
      (libsource (lib "Capacitors") (part "Capacitor - non polarized"))
    )
    (comp (ref "C461")
      (value "100nF")
      (footprint "CAPC0603X33N")
      (description "Non-polarised capacitor")
      (fields
        (field (name "PART NUMBER") "CC0201_100NF_6.3V_10%_X5R")
        (field (name "VOLTAGE") "6.3V")
        (field (name "AUTHOR") "CERN DEM JLC")
      )
      (libsource (lib "Capacitors") (part "Capacitor - non polarized"))
    )
    (comp (ref "C463")
      (value "100nF")
      (footprint "CAPC0603X33N")
      (description "Non-polarised capacitor")
      (fields
        (field (name "PART NUMBER") "CC0201_100NF_6.3V_10%_X5R")
        (field (name "VOLTAGE") "6.3V")
        (field (name "AUTHOR") "CERN DEM JLC")
      )
      (libsource (lib "Capacitors") (part "Capacitor - non polarized"))
    )
    (comp (ref "C512")
      (value "100nF")
      (footprint "CAPC0603X33N")
      (description "Non-polarised capacitor")
      (fields
        (field (name "PART NUMBER") "CC0201_100NF_6.3V_10%_X5R")
        (field (name "VOLTAGE") "6.3V")
        (field (name "AUTHOR") "CERN DEM JLC")
      )
      (libsource (lib "Capacitors") (part "Capacitor - non polarized"))
    )
    (comp (ref "C514")
      (value "100nF")
      (footprint "CAPC0603X33N")
      (description "Non-polarised capacitor")
      (fields
        (field (name "PART NUMBER") "CC0201_100NF_6.3V_10%_X5R")
        (field (name "VOLTAGE") "6.3V")
        (field (name "AUTHOR") "CERN DEM JLC")
      )
      (libsource (lib "Capacitors") (part "Capacitor - non polarized"))
    )
    (comp (ref "C575")
      (value "100nF")
      (footprint "CAPC0603X33N")
      (description "Non-polarised capacitor")
      (fields
        (field (name "PART NUMBER") "CC0201_100NF_6.3V_10%_X5R")
        (field (name "VOLTAGE") "6.3V")
        (field (name "AUTHOR") "CERN DEM JLC")
      )
      (libsource (lib "Capacitors") (part "Capacitor - non polarized"))
    )
    (comp (ref "C590")
      (value "100nF")
      (footprint "CAPC0603X33N")
      (description "Non-polarised capacitor")
      (fields
        (field (name "PART NUMBER") "CC0201_100NF_6.3V_10%_X5R")
        (field (name "VOLTAGE") "6.3V")
        (field (name "AUTHOR") "CERN DEM JLC")
      )
      (libsource (lib "Capacitors") (part "Capacitor - non polarized"))
    )
    (comp (ref "C625")
      (value "100nF")
      (footprint "CAPC0603X33N")
      (description "Non-polarised capacitor")
      (fields
        (field (name "PART NUMBER") "CC0201_100NF_6.3V_10%_X5R")
        (field (name "VOLTAGE") "6.3V")
        (field (name "AUTHOR") "CERN DEM JLC")
      )
      (libsource (lib "Capacitors") (part "Capacitor - non polarized"))
    )
    (comp (ref "C626")
      (value "100nF")
      (footprint "CAPC0603X33N")
      (description "Non-polarised capacitor")
      (fields
        (field (name "PART NUMBER") "CC0201_100NF_6.3V_10%_X5R")
        (field (name "VOLTAGE") "6.3V")
        (field (name "AUTHOR") "CERN DEM JLC")
      )
      (libsource (lib "Capacitors") (part "Capacitor - non polarized"))
    )
    (comp (ref "C627")
      (value "100nF")
      (footprint "CAPC0603X33N")
      (description "Non-polarised capacitor")
      (fields
        (field (name "PART NUMBER") "CC0201_100NF_6.3V_10%_X5R")
        (field (name "VOLTAGE") "6.3V")
        (field (name "AUTHOR") "CERN DEM JLC")
      )
      (libsource (lib "Capacitors") (part "Capacitor - non polarized"))
    )
    (comp (ref "C628")
      (value "100nF")
      (footprint "CAPC0603X33N")
      (description "Non-polarised capacitor")
      (fields
        (field (name "PART NUMBER") "CC0201_100NF_6.3V_10%_X5R")
        (field (name "VOLTAGE") "6.3V")
        (field (name "AUTHOR") "CERN DEM JLC")
      )
      (libsource (lib "Capacitors") (part "Capacitor - non polarized"))
    )
    (comp (ref "C629")
      (value "100nF")
      (footprint "CAPC0603X33N")
      (description "Non-polarised capacitor")
      (fields
        (field (name "PART NUMBER") "CC0201_100NF_6.3V_10%_X5R")
        (field (name "VOLTAGE") "6.3V")
        (field (name "AUTHOR") "CERN DEM JLC")
      )
      (libsource (lib "Capacitors") (part "Capacitor - non polarized"))
    )
    (comp (ref "C630")
      (value "100nF")
      (footprint "CAPC0603X33N")
      (description "Non-polarised capacitor")
      (fields
        (field (name "PART NUMBER") "CC0201_100NF_6.3V_10%_X5R")
        (field (name "VOLTAGE") "6.3V")
        (field (name "AUTHOR") "CERN DEM JLC")
      )
      (libsource (lib "Capacitors") (part "Capacitor - non polarized"))
    )
    (comp (ref "C631")
      (value "100nF")
      (footprint "CAPC0603X33N")
      (description "Non-polarised capacitor")
      (fields
        (field (name "PART NUMBER") "CC0201_100NF_6.3V_10%_X5R")
        (field (name "VOLTAGE") "6.3V")
        (field (name "AUTHOR") "CERN DEM JLC")
      )
      (libsource (lib "Capacitors") (part "Capacitor - non polarized"))
    )
    (comp (ref "C632")
      (value "100nF")
      (footprint "CAPC0603X33N")
      (description "Non-polarised capacitor")
      (fields
        (field (name "PART NUMBER") "CC0201_100NF_6.3V_10%_X5R")
        (field (name "VOLTAGE") "6.3V")
        (field (name "AUTHOR") "CERN DEM JLC")
      )
      (libsource (lib "Capacitors") (part "Capacitor - non polarized"))
    )
    (comp (ref "C633")
      (value "100nF")
      (footprint "CAPC0603X33N")
      (description "Non-polarised capacitor")
      (fields
        (field (name "PART NUMBER") "CC0201_100NF_6.3V_10%_X5R")
        (field (name "VOLTAGE") "6.3V")
        (field (name "AUTHOR") "CERN DEM JLC")
      )
      (libsource (lib "Capacitors") (part "Capacitor - non polarized"))
    )
    (comp (ref "C751")
      (value "100nF")
      (footprint "CAPC0603X33N")
      (description "Non-polarised capacitor")
      (fields
        (field (name "PART NUMBER") "CC0201_100NF_6.3V_10%_X5R")
        (field (name "VOLTAGE") "6.3V")
        (field (name "AUTHOR") "CERN DEM JLC")
      )
      (libsource (lib "Capacitors") (part "Capacitor - non polarized"))
    )
    (comp (ref "C752")
      (value "100nF")
      (footprint "CAPC0603X33N")
      (description "Non-polarised capacitor")
      (fields
        (field (name "PART NUMBER") "CC0201_100NF_6.3V_10%_X5R")
        (field (name "VOLTAGE") "6.3V")
        (field (name "AUTHOR") "CERN DEM JLC")
      )
      (libsource (lib "Capacitors") (part "Capacitor - non polarized"))
    )
    (comp (ref "C753")
      (value "100nF")
      (footprint "CAPC0603X33N")
      (description "Non-polarised capacitor")
      (fields
        (field (name "PART NUMBER") "CC0201_100NF_6.3V_10%_X5R")
        (field (name "VOLTAGE") "6.3V")
        (field (name "AUTHOR") "CERN DEM JLC")
      )
      (libsource (lib "Capacitors") (part "Capacitor - non polarized"))
    )
    (comp (ref "C777")
      (value "100nF")
      (footprint "CAPC0603X33N")
      (description "Non-polarised capacitor")
      (fields
        (field (name "PART NUMBER") "CC0201_100NF_6.3V_10%_X5R")
        (field (name "VOLTAGE") "6.3V")
        (field (name "AUTHOR") "CERN DEM JLC")
      )
      (libsource (lib "Capacitors") (part "Capacitor - non polarized"))
    )
    (comp (ref "C778")
      (value "100nF")
      (footprint "CAPC0603X33N")
      (description "Non-polarised capacitor")
      (fields
        (field (name "PART NUMBER") "CC0201_100NF_6.3V_10%_X5R")
        (field (name "VOLTAGE") "6.3V")
        (field (name "AUTHOR") "CERN DEM JLC")
      )
      (libsource (lib "Capacitors") (part "Capacitor - non polarized"))
    )
    (comp (ref "C779")
      (value "100nF")
      (footprint "CAPC0603X33N")
      (description "Non-polarised capacitor")
      (fields
        (field (name "PART NUMBER") "CC0201_100NF_6.3V_10%_X5R")
        (field (name "VOLTAGE") "6.3V")
        (field (name "AUTHOR") "CERN DEM JLC")
      )
      (libsource (lib "Capacitors") (part "Capacitor - non polarized"))
    )
    (comp (ref "C780")
      (value "100nF")
      (footprint "CAPC0603X33N")
      (description "Non-polarised capacitor")
      (fields
        (field (name "PART NUMBER") "CC0201_100NF_6.3V_10%_X5R")
        (field (name "VOLTAGE") "6.3V")
        (field (name "AUTHOR") "CERN DEM JLC")
      )
      (libsource (lib "Capacitors") (part "Capacitor - non polarized"))
    )
    (comp (ref "C781")
      (value "100nF")
      (footprint "CAPC0603X33N")
      (description "Non-polarised capacitor")
      (fields
        (field (name "PART NUMBER") "CC0201_100NF_6.3V_10%_X5R")
        (field (name "VOLTAGE") "6.3V")
        (field (name "AUTHOR") "CERN DEM JLC")
      )
      (libsource (lib "Capacitors") (part "Capacitor - non polarized"))
    )
    (comp (ref "C782")
      (value "100nF")
      (footprint "CAPC0603X33N")
      (description "Non-polarised capacitor")
      (fields
        (field (name "PART NUMBER") "CC0201_100NF_6.3V_10%_X5R")
        (field (name "VOLTAGE") "6.3V")
        (field (name "AUTHOR") "CERN DEM JLC")
      )
      (libsource (lib "Capacitors") (part "Capacitor - non polarized"))
    )
    (comp (ref "C783")
      (value "100nF")
      (footprint "CAPC0603X33N")
      (description "Non-polarised capacitor")
      (fields
        (field (name "PART NUMBER") "CC0201_100NF_6.3V_10%_X5R")
        (field (name "VOLTAGE") "6.3V")
        (field (name "AUTHOR") "CERN DEM JLC")
      )
      (libsource (lib "Capacitors") (part "Capacitor - non polarized"))
    )
    (comp (ref "C784")
      (value "100nF")
      (footprint "CAPC0603X33N")
      (description "Non-polarised capacitor")
      (fields
        (field (name "PART NUMBER") "CC0201_100NF_6.3V_10%_X5R")
        (field (name "VOLTAGE") "6.3V")
        (field (name "AUTHOR") "CERN DEM JLC")
      )
      (libsource (lib "Capacitors") (part "Capacitor - non polarized"))
    )
    (comp (ref "C785")
      (value "100nF")
      (footprint "CAPC0603X33N")
      (description "Non-polarised capacitor")
      (fields
        (field (name "PART NUMBER") "CC0201_100NF_6.3V_10%_X5R")
        (field (name "VOLTAGE") "6.3V")
        (field (name "AUTHOR") "CERN DEM JLC")
      )
      (libsource (lib "Capacitors") (part "Capacitor - non polarized"))
    )
    (comp (ref "C786")
      (value "100nF")
      (footprint "CAPC0603X33N")
      (description "Non-polarised capacitor")
      (fields
        (field (name "PART NUMBER") "CC0201_100NF_6.3V_10%_X5R")
        (field (name "VOLTAGE") "6.3V")
        (field (name "AUTHOR") "CERN DEM JLC")
      )
      (libsource (lib "Capacitors") (part "Capacitor - non polarized"))
    )
    (comp (ref "C787")
      (value "100nF")
      (footprint "CAPC0603X33N")
      (description "Non-polarised capacitor")
      (fields
        (field (name "PART NUMBER") "CC0201_100NF_6.3V_10%_X5R")
        (field (name "VOLTAGE") "6.3V")
        (field (name "AUTHOR") "CERN DEM JLC")
      )
      (libsource (lib "Capacitors") (part "Capacitor - non polarized"))
    )
    (comp (ref "C788")
      (value "100nF")
      (footprint "CAPC0603X33N")
      (description "Non-polarised capacitor")
      (fields
        (field (name "PART NUMBER") "CC0201_100NF_6.3V_10%_X5R")
        (field (name "VOLTAGE") "6.3V")
        (field (name "AUTHOR") "CERN DEM JLC")
      )
      (libsource (lib "Capacitors") (part "Capacitor - non polarized"))
    )
    (comp (ref "C789")
      (value "100nF")
      (footprint "CAPC0603X33N")
      (description "Non-polarised capacitor")
      (fields
        (field (name "PART NUMBER") "CC0201_100NF_6.3V_10%_X5R")
        (field (name "VOLTAGE") "6.3V")
        (field (name "AUTHOR") "CERN DEM JLC")
      )
      (libsource (lib "Capacitors") (part "Capacitor - non polarized"))
    )
    (comp (ref "C790")
      (value "100nF")
      (footprint "CAPC0603X33N")
      (description "Non-polarised capacitor")
      (fields
        (field (name "PART NUMBER") "CC0201_100NF_6.3V_10%_X5R")
        (field (name "VOLTAGE") "6.3V")
        (field (name "AUTHOR") "CERN DEM JLC")
      )
      (libsource (lib "Capacitors") (part "Capacitor - non polarized"))
    )
    (comp (ref "C791")
      (value "100nF")
      (footprint "CAPC0603X33N")
      (description "Non-polarised capacitor")
      (fields
        (field (name "PART NUMBER") "CC0201_100NF_6.3V_10%_X5R")
        (field (name "VOLTAGE") "6.3V")
        (field (name "AUTHOR") "CERN DEM JLC")
      )
      (libsource (lib "Capacitors") (part "Capacitor - non polarized"))
    )
    (comp (ref "C792")
      (value "100nF")
      (footprint "CAPC0603X33N")
      (description "Non-polarised capacitor")
      (fields
        (field (name "PART NUMBER") "CC0201_100NF_6.3V_10%_X5R")
        (field (name "VOLTAGE") "6.3V")
        (field (name "AUTHOR") "CERN DEM JLC")
      )
      (libsource (lib "Capacitors") (part "Capacitor - non polarized"))
    )
    (comp (ref "C793")
      (value "100nF")
      (footprint "CAPC0603X33N")
      (description "Non-polarised capacitor")
      (fields
        (field (name "PART NUMBER") "CC0201_100NF_6.3V_10%_X5R")
        (field (name "VOLTAGE") "6.3V")
        (field (name "AUTHOR") "CERN DEM JLC")
      )
      (libsource (lib "Capacitors") (part "Capacitor - non polarized"))
    )
    (comp (ref "C794")
      (value "100nF")
      (footprint "CAPC0603X33N")
      (description "Non-polarised capacitor")
      (fields
        (field (name "PART NUMBER") "CC0201_100NF_6.3V_10%_X5R")
        (field (name "VOLTAGE") "6.3V")
        (field (name "AUTHOR") "CERN DEM JLC")
      )
      (libsource (lib "Capacitors") (part "Capacitor - non polarized"))
    )
    (comp (ref "C795")
      (value "100nF")
      (footprint "CAPC0603X33N")
      (description "Non-polarised capacitor")
      (fields
        (field (name "PART NUMBER") "CC0201_100NF_6.3V_10%_X5R")
        (field (name "VOLTAGE") "6.3V")
        (field (name "AUTHOR") "CERN DEM JLC")
      )
      (libsource (lib "Capacitors") (part "Capacitor - non polarized"))
    )
    (comp (ref "C796")
      (value "100nF")
      (footprint "CAPC0603X33N")
      (description "Non-polarised capacitor")
      (fields
        (field (name "PART NUMBER") "CC0201_100NF_6.3V_10%_X5R")
        (field (name "VOLTAGE") "6.3V")
        (field (name "AUTHOR") "CERN DEM JLC")
      )
      (libsource (lib "Capacitors") (part "Capacitor - non polarized"))
    )
    (comp (ref "C797")
      (value "100nF")
      (footprint "CAPC0603X33N")
      (description "Non-polarised capacitor")
      (fields
        (field (name "PART NUMBER") "CC0201_100NF_6.3V_10%_X5R")
        (field (name "VOLTAGE") "6.3V")
        (field (name "AUTHOR") "CERN DEM JLC")
      )
      (libsource (lib "Capacitors") (part "Capacitor - non polarized"))
    )
    (comp (ref "C798")
      (value "100nF")
      (footprint "CAPC0603X33N")
      (description "Non-polarised capacitor")
      (fields
        (field (name "PART NUMBER") "CC0201_100NF_6.3V_10%_X5R")
        (field (name "VOLTAGE") "6.3V")
        (field (name "AUTHOR") "CERN DEM JLC")
      )
      (libsource (lib "Capacitors") (part "Capacitor - non polarized"))
    )
    (comp (ref "C799")
      (value "100nF")
      (footprint "CAPC0603X33N")
      (description "Non-polarised capacitor")
      (fields
        (field (name "PART NUMBER") "CC0201_100NF_6.3V_10%_X5R")
        (field (name "VOLTAGE") "6.3V")
        (field (name "AUTHOR") "CERN DEM JLC")
      )
      (libsource (lib "Capacitors") (part "Capacitor - non polarized"))
    )
    (comp (ref "C800")
      (value "100nF")
      (footprint "CAPC0603X33N")
      (description "Non-polarised capacitor")
      (fields
        (field (name "PART NUMBER") "CC0201_100NF_6.3V_10%_X5R")
        (field (name "VOLTAGE") "6.3V")
        (field (name "AUTHOR") "CERN DEM JLC")
      )
      (libsource (lib "Capacitors") (part "Capacitor - non polarized"))
    )
    (comp (ref "C801")
      (value "100nF")
      (footprint "CAPC0603X33N")
      (description "Non-polarised capacitor")
      (fields
        (field (name "PART NUMBER") "CC0201_100NF_6.3V_10%_X5R")
        (field (name "VOLTAGE") "6.3V")
        (field (name "AUTHOR") "CERN DEM JLC")
      )
      (libsource (lib "Capacitors") (part "Capacitor - non polarized"))
    )
    (comp (ref "C802")
      (value "100nF")
      (footprint "CAPC0603X33N")
      (description "Non-polarised capacitor")
      (fields
        (field (name "PART NUMBER") "CC0201_100NF_6.3V_10%_X5R")
        (field (name "VOLTAGE") "6.3V")
        (field (name "AUTHOR") "CERN DEM JLC")
      )
      (libsource (lib "Capacitors") (part "Capacitor - non polarized"))
    )
    (comp (ref "C803")
      (value "100nF")
      (footprint "CAPC0603X33N")
      (description "Non-polarised capacitor")
      (fields
        (field (name "PART NUMBER") "CC0201_100NF_6.3V_10%_X5R")
        (field (name "VOLTAGE") "6.3V")
        (field (name "AUTHOR") "CERN DEM JLC")
      )
      (libsource (lib "Capacitors") (part "Capacitor - non polarized"))
    )
    (comp (ref "C804")
      (value "100nF")
      (footprint "CAPC0603X33N")
      (description "Non-polarised capacitor")
      (fields
        (field (name "PART NUMBER") "CC0201_100NF_6.3V_10%_X5R")
        (field (name "VOLTAGE") "6.3V")
        (field (name "AUTHOR") "CERN DEM JLC")
      )
      (libsource (lib "Capacitors") (part "Capacitor - non polarized"))
    )
    (comp (ref "C805")
      (value "100nF")
      (footprint "CAPC0603X33N")
      (description "Non-polarised capacitor")
      (fields
        (field (name "PART NUMBER") "CC0201_100NF_6.3V_10%_X5R")
        (field (name "VOLTAGE") "6.3V")
        (field (name "AUTHOR") "CERN DEM JLC")
      )
      (libsource (lib "Capacitors") (part "Capacitor - non polarized"))
    )
    (comp (ref "C806")
      (value "100nF")
      (footprint "CAPC0603X33N")
      (description "Non-polarised capacitor")
      (fields
        (field (name "PART NUMBER") "CC0201_100NF_6.3V_10%_X5R")
        (field (name "VOLTAGE") "6.3V")
        (field (name "AUTHOR") "CERN DEM JLC")
      )
      (libsource (lib "Capacitors") (part "Capacitor - non polarized"))
    )
    (comp (ref "C807")
      (value "100nF")
      (footprint "CAPC0603X33N")
      (description "Non-polarised capacitor")
      (fields
        (field (name "PART NUMBER") "CC0201_100NF_6.3V_10%_X5R")
        (field (name "VOLTAGE") "6.3V")
        (field (name "AUTHOR") "CERN DEM JLC")
      )
      (libsource (lib "Capacitors") (part "Capacitor - non polarized"))
    )
    (comp (ref "C808")
      (value "100nF")
      (footprint "CAPC0603X33N")
      (description "Non-polarised capacitor")
      (fields
        (field (name "PART NUMBER") "CC0201_100NF_6.3V_10%_X5R")
        (field (name "VOLTAGE") "6.3V")
        (field (name "AUTHOR") "CERN DEM JLC")
      )
      (libsource (lib "Capacitors") (part "Capacitor - non polarized"))
    )
    (comp (ref "C809")
      (value "100nF")
      (footprint "CAPC0603X33N")
      (description "Non-polarised capacitor")
      (fields
        (field (name "PART NUMBER") "CC0201_100NF_6.3V_10%_X5R")
        (field (name "VOLTAGE") "6.3V")
        (field (name "AUTHOR") "CERN DEM JLC")
      )
      (libsource (lib "Capacitors") (part "Capacitor - non polarized"))
    )
    (comp (ref "C810")
      (value "100nF")
      (footprint "CAPC0603X33N")
      (description "Non-polarised capacitor")
      (fields
        (field (name "PART NUMBER") "CC0201_100NF_6.3V_10%_X5R")
        (field (name "VOLTAGE") "6.3V")
        (field (name "AUTHOR") "CERN DEM JLC")
      )
      (libsource (lib "Capacitors") (part "Capacitor - non polarized"))
    )
    (comp (ref "C811")
      (value "100nF")
      (footprint "CAPC0603X33N")
      (description "Non-polarised capacitor")
      (fields
        (field (name "PART NUMBER") "CC0201_100NF_6.3V_10%_X5R")
        (field (name "VOLTAGE") "6.3V")
        (field (name "AUTHOR") "CERN DEM JLC")
      )
      (libsource (lib "Capacitors") (part "Capacitor - non polarized"))
    )
    (comp (ref "C812")
      (value "100nF")
      (footprint "CAPC0603X33N")
      (description "Non-polarised capacitor")
      (fields
        (field (name "PART NUMBER") "CC0201_100NF_6.3V_10%_X5R")
        (field (name "VOLTAGE") "6.3V")
        (field (name "AUTHOR") "CERN DEM JLC")
      )
      (libsource (lib "Capacitors") (part "Capacitor - non polarized"))
    )
    (comp (ref "C822")
      (value "100nF")
      (footprint "CAPC0603X33N")
      (description "Non-polarised capacitor")
      (fields
        (field (name "PART NUMBER") "CC0201_100NF_6.3V_10%_X5R")
        (field (name "VOLTAGE") "6.3V")
        (field (name "AUTHOR") "CERN DEM JLC")
      )
      (libsource (lib "Capacitors") (part "Capacitor - non polarized"))
    )
    (comp (ref "C823")
      (value "100nF")
      (footprint "CAPC0603X33N")
      (description "Non-polarised capacitor")
      (fields
        (field (name "PART NUMBER") "CC0201_100NF_6.3V_10%_X5R")
        (field (name "VOLTAGE") "6.3V")
        (field (name "AUTHOR") "CERN DEM JLC")
      )
      (libsource (lib "Capacitors") (part "Capacitor - non polarized"))
    )
    (comp (ref "C824")
      (value "100nF")
      (footprint "CAPC0603X33N")
      (description "Non-polarised capacitor")
      (fields
        (field (name "PART NUMBER") "CC0201_100NF_6.3V_10%_X5R")
        (field (name "VOLTAGE") "6.3V")
        (field (name "AUTHOR") "CERN DEM JLC")
      )
      (libsource (lib "Capacitors") (part "Capacitor - non polarized"))
    )
    (comp (ref "C825")
      (value "100nF")
      (footprint "CAPC0603X33N")
      (description "Non-polarised capacitor")
      (fields
        (field (name "PART NUMBER") "CC0201_100NF_6.3V_10%_X5R")
        (field (name "VOLTAGE") "6.3V")
        (field (name "AUTHOR") "CERN DEM JLC")
      )
      (libsource (lib "Capacitors") (part "Capacitor - non polarized"))
    )
    (comp (ref "C826")
      (value "100nF")
      (footprint "CAPC0603X33N")
      (description "Non-polarised capacitor")
      (fields
        (field (name "PART NUMBER") "CC0201_100NF_6.3V_10%_X5R")
        (field (name "VOLTAGE") "6.3V")
        (field (name "AUTHOR") "CERN DEM JLC")
      )
      (libsource (lib "Capacitors") (part "Capacitor - non polarized"))
    )
    (comp (ref "C827")
      (value "100nF")
      (footprint "CAPC0603X33N")
      (description "Non-polarised capacitor")
      (fields
        (field (name "PART NUMBER") "CC0201_100NF_6.3V_10%_X5R")
        (field (name "VOLTAGE") "6.3V")
        (field (name "AUTHOR") "CERN DEM JLC")
      )
      (libsource (lib "Capacitors") (part "Capacitor - non polarized"))
    )
    (comp (ref "C828")
      (value "100nF")
      (footprint "CAPC0603X33N")
      (description "Non-polarised capacitor")
      (fields
        (field (name "PART NUMBER") "CC0201_100NF_6.3V_10%_X5R")
        (field (name "VOLTAGE") "6.3V")
        (field (name "AUTHOR") "CERN DEM JLC")
      )
      (libsource (lib "Capacitors") (part "Capacitor - non polarized"))
    )
    (comp (ref "C829")
      (value "100nF")
      (footprint "CAPC0603X33N")
      (description "Non-polarised capacitor")
      (fields
        (field (name "PART NUMBER") "CC0201_100NF_6.3V_10%_X5R")
        (field (name "VOLTAGE") "6.3V")
        (field (name "AUTHOR") "CERN DEM JLC")
      )
      (libsource (lib "Capacitors") (part "Capacitor - non polarized"))
    )
    (comp (ref "C830")
      (value "100nF")
      (footprint "CAPC0603X33N")
      (description "Non-polarised capacitor")
      (fields
        (field (name "PART NUMBER") "CC0201_100NF_6.3V_10%_X5R")
        (field (name "VOLTAGE") "6.3V")
        (field (name "AUTHOR") "CERN DEM JLC")
      )
      (libsource (lib "Capacitors") (part "Capacitor - non polarized"))
    )
    (comp (ref "C831")
      (value "100nF")
      (footprint "CAPC0603X33N")
      (description "Non-polarised capacitor")
      (fields
        (field (name "PART NUMBER") "CC0201_100NF_6.3V_10%_X5R")
        (field (name "VOLTAGE") "6.3V")
        (field (name "AUTHOR") "CERN DEM JLC")
      )
      (libsource (lib "Capacitors") (part "Capacitor - non polarized"))
    )
    (comp (ref "C832")
      (value "100nF")
      (footprint "CAPC0603X33N")
      (description "Non-polarised capacitor")
      (fields
        (field (name "PART NUMBER") "CC0201_100NF_6.3V_10%_X5R")
        (field (name "VOLTAGE") "6.3V")
        (field (name "AUTHOR") "CERN DEM JLC")
      )
      (libsource (lib "Capacitors") (part "Capacitor - non polarized"))
    )
    (comp (ref "C833")
      (value "100nF")
      (footprint "CAPC0603X33N")
      (description "Non-polarised capacitor")
      (fields
        (field (name "PART NUMBER") "CC0201_100NF_6.3V_10%_X5R")
        (field (name "VOLTAGE") "6.3V")
        (field (name "AUTHOR") "CERN DEM JLC")
      )
      (libsource (lib "Capacitors") (part "Capacitor - non polarized"))
    )
    (comp (ref "C834")
      (value "100nF")
      (footprint "CAPC0603X33N")
      (description "Non-polarised capacitor")
      (fields
        (field (name "PART NUMBER") "CC0201_100NF_6.3V_10%_X5R")
        (field (name "VOLTAGE") "6.3V")
        (field (name "AUTHOR") "CERN DEM JLC")
      )
      (libsource (lib "Capacitors") (part "Capacitor - non polarized"))
    )
    (comp (ref "C835")
      (value "100nF")
      (footprint "CAPC0603X33N")
      (description "Non-polarised capacitor")
      (fields
        (field (name "PART NUMBER") "CC0201_100NF_6.3V_10%_X5R")
        (field (name "VOLTAGE") "6.3V")
        (field (name "AUTHOR") "CERN DEM JLC")
      )
      (libsource (lib "Capacitors") (part "Capacitor - non polarized"))
    )
    (comp (ref "C836")
      (value "100nF")
      (footprint "CAPC0603X33N")
      (description "Non-polarised capacitor")
      (fields
        (field (name "PART NUMBER") "CC0201_100NF_6.3V_10%_X5R")
        (field (name "VOLTAGE") "6.3V")
        (field (name "AUTHOR") "CERN DEM JLC")
      )
      (libsource (lib "Capacitors") (part "Capacitor - non polarized"))
    )
    (comp (ref "C837")
      (value "100nF")
      (footprint "CAPC0603X33N")
      (description "Non-polarised capacitor")
      (fields
        (field (name "PART NUMBER") "CC0201_100NF_6.3V_10%_X5R")
        (field (name "VOLTAGE") "6.3V")
        (field (name "AUTHOR") "CERN DEM JLC")
      )
      (libsource (lib "Capacitors") (part "Capacitor - non polarized"))
    )
    (comp (ref "C838")
      (value "100nF")
      (footprint "CAPC0603X33N")
      (description "Non-polarised capacitor")
      (fields
        (field (name "PART NUMBER") "CC0201_100NF_6.3V_10%_X5R")
        (field (name "VOLTAGE") "6.3V")
        (field (name "AUTHOR") "CERN DEM JLC")
      )
      (libsource (lib "Capacitors") (part "Capacitor - non polarized"))
    )
    (comp (ref "C839")
      (value "100nF")
      (footprint "CAPC0603X33N")
      (description "Non-polarised capacitor")
      (fields
        (field (name "PART NUMBER") "CC0201_100NF_6.3V_10%_X5R")
        (field (name "VOLTAGE") "6.3V")
        (field (name "AUTHOR") "CERN DEM JLC")
      )
      (libsource (lib "Capacitors") (part "Capacitor - non polarized"))
    )
    (comp (ref "C840")
      (value "100nF")
      (footprint "CAPC0603X33N")
      (description "Non-polarised capacitor")
      (fields
        (field (name "PART NUMBER") "CC0201_100NF_6.3V_10%_X5R")
        (field (name "VOLTAGE") "6.3V")
        (field (name "AUTHOR") "CERN DEM JLC")
      )
      (libsource (lib "Capacitors") (part "Capacitor - non polarized"))
    )
    (comp (ref "C841")
      (value "100nF")
      (footprint "CAPC0603X33N")
      (description "Non-polarised capacitor")
      (fields
        (field (name "PART NUMBER") "CC0201_100NF_6.3V_10%_X5R")
        (field (name "VOLTAGE") "6.3V")
        (field (name "AUTHOR") "CERN DEM JLC")
      )
      (libsource (lib "Capacitors") (part "Capacitor - non polarized"))
    )
    (comp (ref "C883")
      (value "100nF")
      (footprint "CAPC0603X33N")
      (description "Non-polarised capacitor")
      (fields
        (field (name "PART NUMBER") "CC0201_100NF_6.3V_10%_X5R")
        (field (name "VOLTAGE") "6.3V")
        (field (name "AUTHOR") "CERN DEM JLC")
      )
      (libsource (lib "Capacitors") (part "Capacitor - non polarized"))
    )
    (comp (ref "C884")
      (value "100nF")
      (footprint "CAPC0603X33N")
      (description "Non-polarised capacitor")
      (fields
        (field (name "PART NUMBER") "CC0201_100NF_6.3V_10%_X5R")
        (field (name "VOLTAGE") "6.3V")
        (field (name "AUTHOR") "CERN DEM JLC")
      )
      (libsource (lib "Capacitors") (part "Capacitor - non polarized"))
    )
    (comp (ref "C885")
      (value "100nF")
      (footprint "CAPC0603X33N")
      (description "Non-polarised capacitor")
      (fields
        (field (name "PART NUMBER") "CC0201_100NF_6.3V_10%_X5R")
        (field (name "VOLTAGE") "6.3V")
        (field (name "AUTHOR") "CERN DEM JLC")
      )
      (libsource (lib "Capacitors") (part "Capacitor - non polarized"))
    )
    (comp (ref "C886")
      (value "100nF")
      (footprint "CAPC0603X33N")
      (description "Non-polarised capacitor")
      (fields
        (field (name "PART NUMBER") "CC0201_100NF_6.3V_10%_X5R")
        (field (name "VOLTAGE") "6.3V")
        (field (name "AUTHOR") "CERN DEM JLC")
      )
      (libsource (lib "Capacitors") (part "Capacitor - non polarized"))
    )
    (comp (ref "IC2")
      (value "XC7A200T-3FFG1156C")
      (footprint "BGA1156C100P34X34_3500X3500X335")
      (description "Artix-6 FPGA, 16 GTPs, 600 User I/Os, 1156-Pin BGA, Speed Grade 2, Commercial Grade, Pb-Free")
      (fields
        (field (name "MANUFACTURER") "XILINX")
        (field (name "MANUFACTURER PART NUMBER") "XC7A350T-2FFG1156C")
        (field (name "AUTHOR") "CERN DEM JLC")
      )
      (libsource (lib "AMC_FMC_Carrier") (part "XC7A200T-3FFG1156C"))
    )
    (comp (ref "J18")
      (value "U.FL")
      (footprint "HIROSE_U.FL-R-SMT-1(10)")
      (fields
        (field (name "PART NUMBER") "HIROSE_U.FL-R-SMT-1(10)")
        (field (name "MANUFACTURER") "HIROSE (HRS)")
        (field (name "MANUFACTURER PART NUMBER") "U.FL-R-SMT-1(10)")
        (field (name "AUTHOR") "CERN DEM JLC")
      )
      (libsource (lib "Connectors") (part "Coax_1Male_1Shield"))
    )
    (comp (ref "J19")
      (value "U.FL")
      (footprint "HIROSE_U.FL-R-SMT-1(10)")
      (fields
        (field (name "PART NUMBER") "HIROSE_U.FL-R-SMT-1(10)")
        (field (name "MANUFACTURER") "HIROSE (HRS)")
        (field (name "MANUFACTURER PART NUMBER") "U.FL-R-SMT-1(10)")
        (field (name "AUTHOR") "CERN DEM JLC")
      )
      (libsource (lib "Connectors") (part "Coax_1Male_1Shield"))
    )
    (comp (ref "J20")
      (value "U.FL")
      (footprint "HIROSE_U.FL-R-SMT-1(10)")
      (fields
        (field (name "PART NUMBER") "HIROSE_U.FL-R-SMT-1(10)")
        (field (name "MANUFACTURER") "HIROSE (HRS)")
        (field (name "MANUFACTURER PART NUMBER") "U.FL-R-SMT-1(10)")
        (field (name "AUTHOR") "CERN DEM JLC")
      )
      (libsource (lib "Connectors") (part "Coax_1Male_1Shield"))
    )
    (comp (ref "J21")
      (value "U.FL")
      (footprint "HIROSE_U.FL-R-SMT-1(10)")
      (fields
        (field (name "PART NUMBER") "HIROSE_U.FL-R-SMT-1(10)")
        (field (name "MANUFACTURER") "HIROSE (HRS)")
        (field (name "MANUFACTURER PART NUMBER") "U.FL-R-SMT-1(10)")
        (field (name "AUTHOR") "CERN DEM JLC")
      )
      (libsource (lib "Connectors") (part "Coax_1Male_1Shield"))
    )
    (comp (ref "R142")
      (value "100")
      (footprint "RESC1005X40N")
      (description "Resistor - 1%")
      (fields
        (field (name "PART NUMBER") "R0402_100R_1%_0.0625W_100PPM")
        (field (name "POWER") "0.0625W")
        (field (name "AUTHOR") "CERN DEM JLC")
      )
      (libsource (lib "Resistors") (part "Resistor - 1%"))
    )
    (comp (ref "R239")
      (value "100")
      (footprint "RESC1005X40N")
      (description "Resistor - 1%")
      (fields
        (field (name "PART NUMBER") "R0402_100R_1%_0.0625W_100PPM")
        (field (name "POWER") "0.0625W")
        (field (name "AUTHOR") "CERN DEM JLC")
      )
      (libsource (lib "Resistors") (part "Resistor - 1%"))
    )
  )
  (nets
    (net (code "13") (name "/125_GTP213_CLK0_N") (class "Default")
      (node (ref "C399") (pin "1") (pinfunction "1_1") (pintype "passive"))
    )
    (net (code "14") (name "/125_GTP213_CLK0_P") (class "Default")
      (node (ref "C397") (pin "1") (pinfunction "1_1") (pintype "passive"))
    )
    (net (code "15") (name "/FCLK_GTP216_CLK0_N") (class "Default")
      (node (ref "C396") (pin "1") (pinfunction "1_1") (pintype "passive"))
    )
    (net (code "16") (name "/FCLK_GTP216_CLK0_P") (class "Default")
      (node (ref "C218") (pin "1") (pinfunction "1_1") (pintype "passive"))
    )
    (net (code "17") (name "/FLEX_GTP113_CLK0_N") (class "Default")
      (node (ref "C413") (pin "1") (pinfunction "1_1") (pintype "passive"))
    )
    (net (code "18") (name "/FLEX_GTP113_CLK0_P") (class "Default")
      (node (ref "C411") (pin "1") (pinfunction "1_1") (pintype "passive"))
    )
    (net (code "19") (name "/FLEX_GTP113_CLK1_N") (class "Default")
      (node (ref "C409") (pin "1") (pinfunction "1_1") (pintype "passive"))
    )
    (net (code "20") (name "/FLEX_GTP113_CLK1_P") (class "Default")
      (node (ref "C402") (pin "1") (pinfunction "1_1") (pintype "passive"))
    )
    (net (code "21") (name "/FLEX_GTP116_CLK1_N") (class "Default")
      (node (ref "C839") (pin "1") (pinfunction "1_1") (pintype "passive"))
    )
    (net (code "22") (name "/FLEX_GTP116_CLK1_P") (class "Default")
      (node (ref "C838") (pin "1") (pinfunction "1_1") (pintype "passive"))
    )
    (net (code "23") (name "/FLEX_GTP213_CLK1_N") (class "Default")
      (node (ref "C220") (pin "1") (pinfunction "1_1") (pintype "passive"))
    )
    (net (code "24") (name "/FLEX_GTP213_CLK1_P") (class "Default")
      (node (ref "C219") (pin "1") (pinfunction "1_1") (pintype "passive"))
    )
    (net (code "25") (name "/FLEX_GTP216_CLK1_N") (class "Default")
      (node (ref "C463") (pin "1") (pinfunction "1_1") (pintype "passive"))
    )
    (net (code "26") (name "/FLEX_GTP216_CLK1_P") (class "Default")
      (node (ref "C461") (pin "1") (pinfunction "1_1") (pintype "passive"))
    )
    (net (code "27") (name "/FMC1_DP0_C2M_N") (class "Default")
      (node (ref "C179") (pin "1") (pinfunction "1_1") (pintype "passive"))
    )
    (net (code "28") (name "/FMC1_DP0_C2M_P") (class "Default")
      (node (ref "C178") (pin "1") (pinfunction "1_1") (pintype "passive"))
    )
    (net (code "29") (name "/FMC1_DP0_M2C_N") (class "Default")
      (node (ref "C181") (pin "1") (pinfunction "1_1") (pintype "passive"))
    )
    (net (code "30") (name "/FMC1_DP0_M2C_P") (class "Default")
      (node (ref "C180") (pin "1") (pinfunction "1_1") (pintype "passive"))
    )
    (net (code "31") (name "/FMC1_DP1_C2M_N") (class "Default")
      (node (ref "C185") (pin "1") (pinfunction "1_1") (pintype "passive"))
    )
    (net (code "32") (name "/FMC1_DP1_C2M_P") (class "Default")
      (node (ref "C184") (pin "1") (pinfunction "1_1") (pintype "passive"))
    )
    (net (code "33") (name "/FMC1_DP1_M2C_N") (class "Default")
      (node (ref "C187") (pin "1") (pinfunction "1_1") (pintype "passive"))
    )
    (net (code "34") (name "/FMC1_DP1_M2C_P") (class "Default")
      (node (ref "C186") (pin "1") (pinfunction "1_1") (pintype "passive"))
    )
    (net (code "35") (name "/FMC1_DP2_C2M_N") (class "Default")
      (node (ref "C191") (pin "1") (pinfunction "1_1") (pintype "passive"))
    )
    (net (code "36") (name "/FMC1_DP2_C2M_P") (class "Default")
      (node (ref "C190") (pin "1") (pinfunction "1_1") (pintype "passive"))
    )
    (net (code "37") (name "/FMC1_DP2_M2C_N") (class "Default")
      (node (ref "C193") (pin "1") (pinfunction "1_1") (pintype "passive"))
    )
    (net (code "38") (name "/FMC1_DP2_M2C_P") (class "Default")
      (node (ref "C192") (pin "1") (pinfunction "1_1") (pintype "passive"))
    )
    (net (code "39") (name "/FMC1_DP3_C2M_N") (class "Default")
      (node (ref "C195") (pin "1") (pinfunction "1_1") (pintype "passive"))
    )
    (net (code "40") (name "/FMC1_DP3_C2M_P") (class "Default")
      (node (ref "C194") (pin "1") (pinfunction "1_1") (pintype "passive"))
    )
    (net (code "41") (name "/FMC1_DP3_M2C_N") (class "Default")
      (node (ref "C197") (pin "1") (pinfunction "1_1") (pintype "passive"))
    )
    (net (code "42") (name "/FMC1_DP3_M2C_P") (class "Default")
      (node (ref "C196") (pin "1") (pinfunction "1_1") (pintype "passive"))
    )
    (net (code "43") (name "/FMC1_GBTCLK0_M2C_N") (class "Default")
      (node (ref "C189") (pin "1") (pinfunction "1_1") (pintype "passive"))
    )
    (net (code "44") (name "/FMC1_GBTCLK0_M2C_P") (class "Default")
      (node (ref "C188") (pin "1") (pinfunction "1_1") (pintype "passive"))
    )
    (net (code "45") (name "/FMC1_GBTCLK1_M2C_N") (class "Default")
      (node (ref "C183") (pin "1") (pinfunction "1_1") (pintype "passive"))
    )
    (net (code "46") (name "/FMC1_GBTCLK1_M2C_P") (class "Default")
      (node (ref "C182") (pin "1") (pinfunction "1_1") (pintype "passive"))
    )
    (net (code "47") (name "/FMC2_DP0_C2M_N") (class "Default")
      (node (ref "C199") (pin "1") (pinfunction "1_1") (pintype "passive"))
    )
    (net (code "48") (name "/FMC2_DP0_C2M_P") (class "Default")
      (node (ref "C198") (pin "1") (pinfunction "1_1") (pintype "passive"))
    )
    (net (code "49") (name "/FMC2_DP0_M2C_N") (class "Default")
      (node (ref "C201") (pin "1") (pinfunction "1_1") (pintype "passive"))
    )
    (net (code "50") (name "/FMC2_DP0_M2C_P") (class "Default")
      (node (ref "C200") (pin "1") (pinfunction "1_1") (pintype "passive"))
    )
    (net (code "51") (name "/FMC2_DP1_C2M_N") (class "Default")
      (node (ref "C205") (pin "1") (pinfunction "1_1") (pintype "passive"))
    )
    (net (code "52") (name "/FMC2_DP1_C2M_P") (class "Default")
      (node (ref "C204") (pin "1") (pinfunction "1_1") (pintype "passive"))
    )
    (net (code "53") (name "/FMC2_DP1_M2C_N") (class "Default")
      (node (ref "C207") (pin "1") (pinfunction "1_1") (pintype "passive"))
    )
    (net (code "54") (name "/FMC2_DP1_M2C_P") (class "Default")
      (node (ref "C206") (pin "1") (pinfunction "1_1") (pintype "passive"))
    )
    (net (code "55") (name "/FMC2_DP2_C2M_N") (class "Default")
      (node (ref "C629") (pin "1") (pinfunction "1_1") (pintype "passive"))
    )
    (net (code "56") (name "/FMC2_DP2_C2M_P") (class "Default")
      (node (ref "C627") (pin "1") (pinfunction "1_1") (pintype "passive"))
    )
    (net (code "57") (name "/FMC2_DP2_M2C_N") (class "Default")
      (node (ref "C633") (pin "1") (pinfunction "1_1") (pintype "passive"))
    )
    (net (code "58") (name "/FMC2_DP2_M2C_P") (class "Default")
      (node (ref "C631") (pin "1") (pinfunction "1_1") (pintype "passive"))
    )
    (net (code "59") (name "/FMC2_DP3_C2M_N") (class "Default")
      (node (ref "C628") (pin "1") (pinfunction "1_1") (pintype "passive"))
    )
    (net (code "60") (name "/FMC2_DP3_C2M_P") (class "Default")
      (node (ref "C626") (pin "1") (pinfunction "1_1") (pintype "passive"))
    )
    (net (code "61") (name "/FMC2_DP3_M2C_N") (class "Default")
      (node (ref "C632") (pin "1") (pinfunction "1_1") (pintype "passive"))
    )
    (net (code "62") (name "/FMC2_DP3_M2C_P") (class "Default")
      (node (ref "C630") (pin "1") (pinfunction "1_1") (pintype "passive"))
    )
    (net (code "63") (name "/FMC2_GBTCLK0_M2C_N") (class "Default")
      (node (ref "C203") (pin "1") (pinfunction "1_1") (pintype "passive"))
    )
    (net (code "64") (name "/FMC2_GBTCLK0_M2C_P") (class "Default")
      (node (ref "C202") (pin "1") (pinfunction "1_1") (pintype "passive"))
    )
    (net (code "65") (name "/FMC2_GBTCLK1_M2C_N") (class "Default")
      (node (ref "C841") (pin "1") (pinfunction "1_1") (pintype "passive"))
    )
    (net (code "66") (name "/FMC2_GBTCLK1_M2C_P") (class "Default")
      (node (ref "C840") (pin "1") (pinfunction "1_1") (pintype "passive"))
    )
    (net (code "67") (name "/GTP0-3_CLK_IN_N") (class "Default")
      (node (ref "C799") (pin "1") (pinfunction "1_1") (pintype "passive"))
    )
    (net (code "68") (name "/GTP0-3_CLK_IN_P") (class "Default")
      (node (ref "C797") (pin "1") (pinfunction "1_1") (pintype "passive"))
    )
    (net (code "69") (name "/GTP0_RX_N") (class "Default")
      (node (ref "C780") (pin "1") (pinfunction "1_1") (pintype "passive"))
    )
    (net (code "70") (name "/GTP0_RX_P") (class "Default")
      (node (ref "C779") (pin "1") (pinfunction "1_1") (pintype "passive"))
    )
    (net (code "71") (name "/GTP0_TX_N") (class "Default")
      (node (ref "C778") (pin "1") (pinfunction "1_1") (pintype "passive"))
    )
    (net (code "72") (name "/GTP0_TX_P") (class "Default")
      (node (ref "C777") (pin "1") (pinfunction "1_1") (pintype "passive"))
    )
    (net (code "73") (name "/GTP1_RX_N") (class "Default")
      (node (ref "C784") (pin "1") (pinfunction "1_1") (pintype "passive"))
    )
    (net (code "74") (name "/GTP1_RX_P") (class "Default")
      (node (ref "C783") (pin "1") (pinfunction "1_1") (pintype "passive"))
    )
    (net (code "75") (name "/GTP1_TX_N") (class "Default")
      (node (ref "C782") (pin "1") (pinfunction "1_1") (pintype "passive"))
    )
    (net (code "76") (name "/GTP1_TX_P") (class "Default")
      (node (ref "C781") (pin "1") (pinfunction "1_1") (pintype "passive"))
    )
    (net (code "77") (name "/GTP2_RX_N") (class "Default")
      (node (ref "C788") (pin "1") (pinfunction "1_1") (pintype "passive"))
    )
    (net (code "78") (name "/GTP2_RX_P") (class "Default")
      (node (ref "C787") (pin "1") (pinfunction "1_1") (pintype "passive"))
    )
    (net (code "79") (name "/GTP2_TX_N") (class "Default")
      (node (ref "C786") (pin "1") (pinfunction "1_1") (pintype "passive"))
    )
    (net (code "80") (name "/GTP2_TX_P") (class "Default")
      (node (ref "C785") (pin "1") (pinfunction "1_1") (pintype "passive"))
    )
    (net (code "81") (name "/GTP3_RX_N") (class "Default")
      (node (ref "C793") (pin "1") (pinfunction "1_1") (pintype "passive"))
    )
    (net (code "82") (name "/GTP3_RX_P") (class "Default")
      (node (ref "C791") (pin "1") (pinfunction "1_1") (pintype "passive"))
    )
    (net (code "83") (name "/GTP3_TX_N") (class "Default")
      (node (ref "C790") (pin "1") (pinfunction "1_1") (pintype "passive"))
    )
    (net (code "84") (name "/GTP3_TX_P") (class "Default")
      (node (ref "C789") (pin "1") (pinfunction "1_1") (pintype "passive"))
    )
    (net (code "85") (name "/GTP4-7_CLK_IN_N") (class "Default")
      (node (ref "C794") (pin "1") (pinfunction "1_1") (pintype "passive"))
    )
    (net (code "86") (name "/GTP4-7_CLK_IN_P") (class "Default")
      (node (ref "C792") (pin "1") (pinfunction "1_1") (pintype "passive"))
    )
    (net (code "87") (name "/GTP4_RX_N") (class "Default")
      (node (ref "C800") (pin "1") (pinfunction "1_1") (pintype "passive"))
    )
    (net (code "88") (name "/GTP4_RX_P") (class "Default")
      (node (ref "C798") (pin "1") (pinfunction "1_1") (pintype "passive"))
    )
    (net (code "89") (name "/GTP4_TX_N") (class "Default")
      (node (ref "C796") (pin "1") (pinfunction "1_1") (pintype "passive"))
    )
    (net (code "90") (name "/GTP4_TX_P") (class "Default")
      (node (ref "C795") (pin "1") (pinfunction "1_1") (pintype "passive"))
    )
    (net (code "91") (name "/GTP5_RX_N") (class "Default")
      (node (ref "C804") (pin "1") (pinfunction "1_1") (pintype "passive"))
    )
    (net (code "92") (name "/GTP5_RX_P") (class "Default")
      (node (ref "C803") (pin "1") (pinfunction "1_1") (pintype "passive"))
    )
    (net (code "93") (name "/GTP5_TX_N") (class "Default")
      (node (ref "C802") (pin "1") (pinfunction "1_1") (pintype "passive"))
    )
    (net (code "94") (name "/GTP5_TX_P") (class "Default")
      (node (ref "C801") (pin "1") (pinfunction "1_1") (pintype "passive"))
    )
    (net (code "95") (name "/GTP6_RX_N") (class "Default")
      (node (ref "C808") (pin "1") (pinfunction "1_1") (pintype "passive"))
    )
    (net (code "96") (name "/GTP6_RX_P") (class "Default")
      (node (ref "C807") (pin "1") (pinfunction "1_1") (pintype "passive"))
    )
    (net (code "97") (name "/GTP6_TX_N") (class "Default")
      (node (ref "C806") (pin "1") (pinfunction "1_1") (pintype "passive"))
    )
    (net (code "98") (name "/GTP6_TX_P") (class "Default")
      (node (ref "C805") (pin "1") (pinfunction "1_1") (pintype "passive"))
    )
    (net (code "99") (name "/GTP7_RX_N") (class "Default")
      (node (ref "C812") (pin "1") (pinfunction "1_1") (pintype "passive"))
    )
    (net (code "100") (name "/GTP7_RX_P") (class "Default")
      (node (ref "C811") (pin "1") (pinfunction "1_1") (pintype "passive"))
    )
    (net (code "101") (name "/GTP7_TX_N") (class "Default")
      (node (ref "C810") (pin "1") (pinfunction "1_1") (pintype "passive"))
    )
    (net (code "102") (name "/GTP7_TX_P") (class "Default")
      (node (ref "C809") (pin "1") (pinfunction "1_1") (pintype "passive"))
    )
    (net (code "103") (name "/MGT113_CLK0_N") (class "Default")
      (node (ref "C413") (pin "2") (pinfunction "2_2") (pintype "passive"))
      (node (ref "IC2") (pin "AH14") (pinfunction "MGTREFCLK0N_113_AH14") (pintype "input"))
    )
    (net (code "104") (name "/MGT113_CLK0_P") (class "Default")
      (node (ref "C411") (pin "2") (pinfunction "2_2") (pintype "passive"))
      (node (ref "IC2") (pin "AG14") (pinfunction "MGTREFCLK0P_113_AG14") (pintype "input"))
    )
    (net (code "105") (name "/MGT113_CLK1_N") (class "Default")
      (node (ref "C409") (pin "2") (pinfunction "2_2") (pintype "passive"))
      (node (ref "IC2") (pin "AH16") (pinfunction "MGTREFCLK1N_113_AH16") (pintype "input"))
    )
    (net (code "106") (name "/MGT113_CLK1_P") (class "Default")
      (node (ref "C402") (pin "2") (pinfunction "2_2") (pintype "passive"))
      (node (ref "IC2") (pin "AG16") (pinfunction "MGTREFCLK1P_113_AG16") (pintype "input"))
    )
    (net (code "107") (name "/MGT116_CLK0_N") (class "Default")
      (node (ref "C189") (pin "2") (pinfunction "2_2") (pintype "passive"))
      (node (ref "C799") (pin "2") (pinfunction "2_2") (pintype "passive"))
      (node (ref "IC2") (pin "G16") (pinfunction "MGTREFCLK0N_116_G16") (pintype "input"))
    )
    (net (code "108") (name "/MGT116_CLK0_P") (class "Default")
      (node (ref "C188") (pin "2") (pinfunction "2_2") (pintype "passive"))
      (node (ref "C797") (pin "2") (pinfunction "2_2") (pintype "passive"))
      (node (ref "IC2") (pin "H16") (pinfunction "MGTREFCLK0P_116_H16") (pintype "input"))
    )
    (net (code "109") (name "/MGT116_CLK1_N") (class "Default")
      (node (ref "C183") (pin "2") (pinfunction "2_2") (pintype "passive"))
      (node (ref "C839") (pin "2") (pinfunction "2_2") (pintype "passive"))
      (node (ref "IC2") (pin "G14") (pinfunction "MGTREFCLK1N_116_G14") (pintype "input"))
    )
    (net (code "110") (name "/MGT116_CLK1_P") (class "Default")
      (node (ref "C182") (pin "2") (pinfunction "2_2") (pintype "passive"))
      (node (ref "C838") (pin "2") (pinfunction "2_2") (pintype "passive"))
      (node (ref "IC2") (pin "H14") (pinfunction "MGTREFCLK1P_116_H14") (pintype "input"))
    )
    (net (code "111") (name "/MGT213_CLK0_N") (class "Default")
      (node (ref "C203") (pin "2") (pinfunction "2_2") (pintype "passive"))
      (node (ref "C399") (pin "2") (pinfunction "2_2") (pintype "passive"))
      (node (ref "C794") (pin "2") (pinfunction "2_2") (pintype "passive"))
      (node (ref "IC2") (pin "AH20") (pinfunction "MGTREFCLK0N_213_AH20") (pintype "input"))
    )
    (net (code "112") (name "/MGT213_CLK0_P") (class "Default")
      (node (ref "C202") (pin "2") (pinfunction "2_2") (pintype "passive"))
      (node (ref "C397") (pin "2") (pinfunction "2_2") (pintype "passive"))
      (node (ref "C792") (pin "2") (pinfunction "2_2") (pintype "passive"))
      (node (ref "IC2") (pin "AG20") (pinfunction "MGTREFCLK0P_213_AG20") (pintype "input"))
    )
    (net (code "113") (name "/MGT213_CLK1_N") (class "Default")
      (node (ref "C220") (pin "2") (pinfunction "2_2") (pintype "passive"))
      (node (ref "C841") (pin "2") (pinfunction "2_2") (pintype "passive"))
      (node (ref "IC2") (pin "AH18") (pinfunction "MGTREFCLK1N_213_AH18") (pintype "input"))
    )
    (net (code "114") (name "/MGT213_CLK1_P") (class "Default")
      (node (ref "C219") (pin "2") (pinfunction "2_2") (pintype "passive"))
      (node (ref "C840") (pin "2") (pinfunction "2_2") (pintype "passive"))
      (node (ref "IC2") (pin "AG18") (pinfunction "MGTREFCLK1P_213_AG18") (pintype "input"))
    )
    (net (code "115") (name "/MGT216_CLK0_N") (class "Default")
      (node (ref "C396") (pin "2") (pinfunction "2_2") (pintype "passive"))
      (node (ref "IC2") (pin "G18") (pinfunction "MGTREFCLK0N_216_G18") (pintype "input"))
    )
    (net (code "116") (name "/MGT216_CLK0_P") (class "Default")
      (node (ref "C218") (pin "2") (pinfunction "2_2") (pintype "passive"))
      (node (ref "IC2") (pin "H18") (pinfunction "MGTREFCLK0P_216_H18") (pintype "input"))
    )
    (net (code "117") (name "/MGT216_CLK1_N") (class "Default")
      (node (ref "C463") (pin "2") (pinfunction "2_2") (pintype "passive"))
      (node (ref "IC2") (pin "G20") (pinfunction "MGTREFCLK1N_216_G20") (pintype "input"))
    )
    (net (code "118") (name "/MGT216_CLK1_P") (class "Default")
      (node (ref "C461") (pin "2") (pinfunction "2_2") (pintype "passive"))
      (node (ref "IC2") (pin "H20") (pinfunction "MGTREFCLK1P_216_H20") (pintype "input"))
    )
    (net (code "119") (name "/MGTAVTT_R0") (class "Default")
      (node (ref "IC2") (pin "AH22") (pinfunction "MGTRREF_213_AH22") (pintype "input"))
      (node (ref "R239") (pin "2") (pinfunction "2_2") (pintype "passive"))
    )
    (net (code "120") (name "/MGTAVTT_R1") (class "Default")
      (node (ref "IC2") (pin "G22") (pinfunction "MGTRREF_216_G22") (pintype "input"))
      (node (ref "R142") (pin "2") (pinfunction "2_2") (pintype "passive"))
    )
    (net (code "121") (name "/Rx0_N") (class "Default")
      (node (ref "C224") (pin "1") (pinfunction "1_1") (pintype "passive"))
      (node (ref "C884") (pin "1") (pinfunction "1_1") (pintype "passive"))
    )
    (net (code "122") (name "/Rx0_P") (class "Default")
      (node (ref "C223") (pin "1") (pinfunction "1_1") (pintype "passive"))
      (node (ref "C883") (pin "1") (pinfunction "1_1") (pintype "passive"))
    )
    (net (code "123") (name "/Rx1_N") (class "Default")
      (node (ref "C625") (pin "1") (pinfunction "1_1") (pintype "passive"))
    )
    (net (code "124") (name "/Rx1_P") (class "Default")
      (node (ref "C228") (pin "1") (pinfunction "1_1") (pintype "passive"))
    )
    (net (code "125") (name "/Rx2_N") (class "Default")
      (node (ref "C512") (pin "2") (pinfunction "2_2") (pintype "passive"))
    )
    (net (code "126") (name "/Rx2_P") (class "Default")
      (node (ref "C455") (pin "2") (pinfunction "2_2") (pintype "passive"))
    )
    (net (code "127") (name "/Rx3_N") (class "Default")
      (node (ref "C751") (pin "2") (pinfunction "2_2") (pintype "passive"))
    )
    (net (code "128") (name "/Rx3_P") (class "Default")
      (node (ref "C590") (pin "2") (pinfunction "2_2") (pintype "passive"))
    )
    (net (code "129") (name "/Rx4_N") (class "Default")
      (node (ref "C337") (pin "1") (pinfunction "1_1") (pintype "passive"))
    )
    (net (code "130") (name "/Rx4_P") (class "Default")
      (node (ref "C336") (pin "1") (pinfunction "1_1") (pintype "passive"))
    )
    (net (code "131") (name "/Rx5_N") (class "Default")
      (node (ref "C341") (pin "1") (pinfunction "1_1") (pintype "passive"))
    )
    (net (code "132") (name "/Rx5_P") (class "Default")
      (node (ref "C340") (pin "1") (pinfunction "1_1") (pintype "passive"))
    )
    (net (code "133") (name "/Rx6_N") (class "Default")
      (node (ref "C349") (pin "1") (pinfunction "1_1") (pintype "passive"))
    )
    (net (code "134") (name "/Rx6_P") (class "Default")
      (node (ref "C348") (pin "1") (pinfunction "1_1") (pintype "passive"))
    )
    (net (code "135") (name "/Rx7_N") (class "Default")
      (node (ref "C345") (pin "1") (pinfunction "1_1") (pintype "passive"))
    )
    (net (code "136") (name "/Rx7_P") (class "Default")
      (node (ref "C344") (pin "1") (pinfunction "1_1") (pintype "passive"))
    )
    (net (code "137") (name "/Rx8_N") (class "Default")
      (node (ref "C321") (pin "1") (pinfunction "1_1") (pintype "passive"))
    )
    (net (code "138") (name "/Rx8_P") (class "Default")
      (node (ref "C320") (pin "1") (pinfunction "1_1") (pintype "passive"))
    )
    (net (code "139") (name "/Rx9_N") (class "Default")
      (node (ref "C325") (pin "1") (pinfunction "1_1") (pintype "passive"))
    )
    (net (code "140") (name "/Rx9_P") (class "Default")
      (node (ref "C324") (pin "1") (pinfunction "1_1") (pintype "passive"))
    )
    (net (code "141") (name "/Rx10_N") (class "Default")
      (node (ref "C329") (pin "1") (pinfunction "1_1") (pintype "passive"))
    )
    (net (code "142") (name "/Rx10_P") (class "Default")
      (node (ref "C328") (pin "1") (pinfunction "1_1") (pintype "passive"))
    )
    (net (code "143") (name "/Rx11_N") (class "Default")
      (node (ref "C333") (pin "1") (pinfunction "1_1") (pintype "passive"))
    )
    (net (code "144") (name "/Rx11_P") (class "Default")
      (node (ref "C332") (pin "1") (pinfunction "1_1") (pintype "passive"))
    )
    (net (code "145") (name "/Rx12_N") (class "Default")
      (node (ref "C825") (pin "1") (pinfunction "1_1") (pintype "passive"))
    )
    (net (code "146") (name "/Rx12_P") (class "Default")
      (node (ref "C824") (pin "1") (pinfunction "1_1") (pintype "passive"))
    )
    (net (code "147") (name "/Rx13_N") (class "Default")
      (node (ref "C833") (pin "1") (pinfunction "1_1") (pintype "passive"))
    )
    (net (code "148") (name "/Rx13_P") (class "Default")
      (node (ref "C832") (pin "1") (pinfunction "1_1") (pintype "passive"))
    )
    (net (code "149") (name "/Rx14_N") (class "Default")
      (node (ref "C829") (pin "1") (pinfunction "1_1") (pintype "passive"))
    )
    (net (code "150") (name "/Rx14_P") (class "Default")
      (node (ref "C828") (pin "1") (pinfunction "1_1") (pintype "passive"))
    )
    (net (code "151") (name "/Rx15_N") (class "Default")
      (node (ref "C837") (pin "1") (pinfunction "1_1") (pintype "passive"))
    )
    (net (code "152") (name "/Rx15_P") (class "Default")
      (node (ref "C836") (pin "1") (pinfunction "1_1") (pintype "passive"))
    )
    (net (code "153") (name "/Rx113_0_N") (class "Default")
      (node (ref "C321") (pin "2") (pinfunction "2_2") (pintype "passive"))
      (node (ref "C751") (pin "1") (pinfunction "1_1") (pintype "passive"))
      (node (ref "IC2") (pin "AK17") (pinfunction "MGTPRXN0_113_AK17") (pintype "input"))
    )
    (net (code "154") (name "/Rx113_0_P") (class "Default")
      (node (ref "C320") (pin "2") (pinfunction "2_2") (pintype "passive"))
      (node (ref "C590") (pin "1") (pinfunction "1_1") (pintype "passive"))
      (node (ref "IC2") (pin "AJ17") (pinfunction "MGTPRXP0_113_AJ17") (pintype "input"))
    )
    (net (code "155") (name "/Rx113_1_N") (class "Default")
      (node (ref "C325") (pin "2") (pinfunction "2_2") (pintype "passive"))
      (node (ref "C512") (pin "1") (pinfunction "1_1") (pintype "passive"))
      (node (ref "IC2") (pin "AM16") (pinfunction "MGTPRXN1_113_AM16") (pintype "input"))
    )
    (net (code "156") (name "/Rx113_1_P") (class "Default")
      (node (ref "C324") (pin "2") (pinfunction "2_2") (pintype "passive"))
      (node (ref "C455") (pin "1") (pinfunction "1_1") (pintype "passive"))
      (node (ref "IC2") (pin "AL16") (pinfunction "MGTPRXP1_113_AL16") (pintype "input"))
    )
    (net (code "157") (name "/Rx113_2_N") (class "Default")
      (node (ref "C329") (pin "2") (pinfunction "2_2") (pintype "passive"))
      (node (ref "C625") (pin "2") (pinfunction "2_2") (pintype "passive"))
      (node (ref "IC2") (pin "AK15") (pinfunction "MGTPRXN2_113_AK15") (pintype "input"))
    )
    (net (code "158") (name "/Rx113_2_P") (class "Default")
      (node (ref "C228") (pin "2") (pinfunction "2_2") (pintype "passive"))
      (node (ref "C328") (pin "2") (pinfunction "2_2") (pintype "passive"))
      (node (ref "IC2") (pin "AJ15") (pinfunction "MGTPRXP2_113_AJ15") (pintype "input"))
    )
    (net (code "159") (name "/Rx113_3_N") (class "Default")
      (node (ref "C224") (pin "2") (pinfunction "2_2") (pintype "passive"))
      (node (ref "C333") (pin "2") (pinfunction "2_2") (pintype "passive"))
      (node (ref "IC2") (pin "AK13") (pinfunction "MGTPRXN3_113_AK13") (pintype "input"))
    )
    (net (code "160") (name "/Rx113_3_P") (class "Default")
      (node (ref "C223") (pin "2") (pinfunction "2_2") (pintype "passive"))
      (node (ref "C332") (pin "2") (pinfunction "2_2") (pintype "passive"))
      (node (ref "IC2") (pin "AJ13") (pinfunction "MGTPRXP3_113_AJ13") (pintype "input"))
    )
    (net (code "161") (name "/Rx116_0_N") (class "Default")
      (node (ref "C197") (pin "2") (pinfunction "2_2") (pintype "passive"))
      (node (ref "C780") (pin "2") (pinfunction "2_2") (pintype "passive"))
      (node (ref "IC2") (pin "E13") (pinfunction "MGTPRXN0_116_E13") (pintype "input"))
    )
    (net (code "162") (name "/Rx116_0_P") (class "Default")
      (node (ref "C196") (pin "2") (pinfunction "2_2") (pintype "passive"))
      (node (ref "C779") (pin "2") (pinfunction "2_2") (pintype "passive"))
      (node (ref "IC2") (pin "F13") (pinfunction "MGTPRXP0_116_F13") (pintype "input"))
    )
    (net (code "163") (name "/Rx116_1_N") (class "Default")
      (node (ref "C193") (pin "2") (pinfunction "2_2") (pintype "passive"))
      (node (ref "C784") (pin "2") (pinfunction "2_2") (pintype "passive"))
      (node (ref "IC2") (pin "E15") (pinfunction "MGTPRXN1_116_E15") (pintype "input"))
    )
    (net (code "164") (name "/Rx116_1_P") (class "Default")
      (node (ref "C192") (pin "2") (pinfunction "2_2") (pintype "passive"))
      (node (ref "C783") (pin "2") (pinfunction "2_2") (pintype "passive"))
      (node (ref "IC2") (pin "F15") (pinfunction "MGTPRXP1_116_F15") (pintype "input"))
    )
    (net (code "165") (name "/Rx116_2_N") (class "Default")
      (node (ref "C187") (pin "2") (pinfunction "2_2") (pintype "passive"))
      (node (ref "C788") (pin "2") (pinfunction "2_2") (pintype "passive"))
      (node (ref "IC2") (pin "C16") (pinfunction "MGTPRXN2_116_C16") (pintype "input"))
    )
    (net (code "166") (name "/Rx116_2_P") (class "Default")
      (node (ref "C186") (pin "2") (pinfunction "2_2") (pintype "passive"))
      (node (ref "C787") (pin "2") (pinfunction "2_2") (pintype "passive"))
      (node (ref "IC2") (pin "D16") (pinfunction "MGTPRXP2_116_D16") (pintype "input"))
    )
    (net (code "167") (name "/Rx116_3_N") (class "Default")
      (node (ref "C181") (pin "2") (pinfunction "2_2") (pintype "passive"))
      (node (ref "C793") (pin "2") (pinfunction "2_2") (pintype "passive"))
      (node (ref "IC2") (pin "E17") (pinfunction "MGTPRXN3_116_E17") (pintype "input"))
    )
    (net (code "168") (name "/Rx116_3_P") (class "Default")
      (node (ref "C180") (pin "2") (pinfunction "2_2") (pintype "passive"))
      (node (ref "C791") (pin "2") (pinfunction "2_2") (pintype "passive"))
      (node (ref "IC2") (pin "F17") (pinfunction "MGTPRXP3_116_F17") (pintype "input"))
    )
    (net (code "169") (name "/Rx213_0_N") (class "Default")
      (node (ref "C201") (pin "2") (pinfunction "2_2") (pintype "passive"))
      (node (ref "C800") (pin "2") (pinfunction "2_2") (pintype "passive"))
      (node (ref "C825") (pin "2") (pinfunction "2_2") (pintype "passive"))
      (node (ref "IC2") (pin "AM18") (pinfunction "MGTPRXN0_213_AM18") (pintype "input"))
    )
    (net (code "170") (name "/Rx213_0_P") (class "Default")
      (node (ref "C200") (pin "2") (pinfunction "2_2") (pintype "passive"))
      (node (ref "C798") (pin "2") (pinfunction "2_2") (pintype "passive"))
      (node (ref "C824") (pin "2") (pinfunction "2_2") (pintype "passive"))
      (node (ref "IC2") (pin "AL18") (pinfunction "MGTPRXP0_213_AL18") (pintype "input"))
    )
    (net (code "171") (name "/Rx213_1_N") (class "Default")
      (node (ref "C207") (pin "2") (pinfunction "2_2") (pintype "passive"))
      (node (ref "C804") (pin "2") (pinfunction "2_2") (pintype "passive"))
      (node (ref "C829") (pin "2") (pinfunction "2_2") (pintype "passive"))
      (node (ref "IC2") (pin "AK19") (pinfunction "MGTPRXN1_213_AK19") (pintype "input"))
    )
    (net (code "172") (name "/Rx213_1_P") (class "Default")
      (node (ref "C206") (pin "2") (pinfunction "2_2") (pintype "passive"))
      (node (ref "C803") (pin "2") (pinfunction "2_2") (pintype "passive"))
      (node (ref "C828") (pin "2") (pinfunction "2_2") (pintype "passive"))
      (node (ref "IC2") (pin "AJ19") (pinfunction "MGTPRXP1_213_AJ19") (pintype "input"))
    )
    (net (code "173") (name "/Rx213_2_N") (class "Default")
      (node (ref "C633") (pin "2") (pinfunction "2_2") (pintype "passive"))
      (node (ref "C808") (pin "2") (pinfunction "2_2") (pintype "passive"))
      (node (ref "C833") (pin "2") (pinfunction "2_2") (pintype "passive"))
      (node (ref "IC2") (pin "AM20") (pinfunction "MGTPRXN2_213_AM20") (pintype "input"))
    )
    (net (code "174") (name "/Rx213_2_P") (class "Default")
      (node (ref "C631") (pin "2") (pinfunction "2_2") (pintype "passive"))
      (node (ref "C807") (pin "2") (pinfunction "2_2") (pintype "passive"))
      (node (ref "C832") (pin "2") (pinfunction "2_2") (pintype "passive"))
      (node (ref "IC2") (pin "AL20") (pinfunction "MGTPRXP2_213_AL20") (pintype "input"))
    )
    (net (code "175") (name "/Rx213_3_N") (class "Default")
      (node (ref "C632") (pin "2") (pinfunction "2_2") (pintype "passive"))
      (node (ref "C812") (pin "2") (pinfunction "2_2") (pintype "passive"))
      (node (ref "C837") (pin "2") (pinfunction "2_2") (pintype "passive"))
      (node (ref "IC2") (pin "AK21") (pinfunction "MGTPRXN3_213_AK21") (pintype "input"))
    )
    (net (code "176") (name "/Rx213_3_P") (class "Default")
      (node (ref "C630") (pin "2") (pinfunction "2_2") (pintype "passive"))
      (node (ref "C811") (pin "2") (pinfunction "2_2") (pintype "passive"))
      (node (ref "C836") (pin "2") (pinfunction "2_2") (pintype "passive"))
      (node (ref "IC2") (pin "AJ21") (pinfunction "MGTPRXP3_213_AJ21") (pintype "input"))
    )
    (net (code "177") (name "/Rx216_0_N") (class "Default")
      (node (ref "C337") (pin "2") (pinfunction "2_2") (pintype "passive"))
      (node (ref "IC2") (pin "E21") (pinfunction "MGTPRXN0_216_E21") (pintype "input"))
    )
    (net (code "178") (name "/Rx216_0_P") (class "Default")
      (node (ref "C336") (pin "2") (pinfunction "2_2") (pintype "passive"))
      (node (ref "IC2") (pin "F21") (pinfunction "MGTPRXP0_216_F21") (pintype "input"))
    )
    (net (code "179") (name "/Rx216_1_N") (class "Default")
      (node (ref "C341") (pin "2") (pinfunction "2_2") (pintype "passive"))
      (node (ref "IC2") (pin "C20") (pinfunction "MGTPRXN1_216_C20") (pintype "input"))
    )
    (net (code "180") (name "/Rx216_1_P") (class "Default")
      (node (ref "C340") (pin "2") (pinfunction "2_2") (pintype "passive"))
      (node (ref "IC2") (pin "D20") (pinfunction "MGTPRXP1_216_D20") (pintype "input"))
    )
    (net (code "181") (name "/Rx216_2_N") (class "Default")
      (node (ref "C349") (pin "2") (pinfunction "2_2") (pintype "passive"))
      (node (ref "IC2") (pin "E19") (pinfunction "MGTPRXN2_216_E19") (pintype "input"))
    )
    (net (code "182") (name "/Rx216_2_P") (class "Default")
      (node (ref "C348") (pin "2") (pinfunction "2_2") (pintype "passive"))
      (node (ref "IC2") (pin "F19") (pinfunction "MGTPRXP2_216_F19") (pintype "input"))
    )
    (net (code "183") (name "/Rx216_3_N") (class "Default")
      (node (ref "C345") (pin "2") (pinfunction "2_2") (pintype "passive"))
      (node (ref "IC2") (pin "C18") (pinfunction "MGTPRXN3_216_C18") (pintype "input"))
    )
    (net (code "184") (name "/Rx216_3_P") (class "Default")
      (node (ref "C344") (pin "2") (pinfunction "2_2") (pintype "passive"))
      (node (ref "IC2") (pin "D18") (pinfunction "MGTPRXP3_216_D18") (pintype "input"))
    )
    (net (code "185") (name "/RxC0_N") (class "Default")
      (node (ref "C884") (pin "2") (pinfunction "2_2") (pintype "passive"))
      (node (ref "J19") (pin "1") (pinfunction "1_1") (pintype "bidirectional"))
    )
    (net (code "186") (name "/RxC0_P") (class "Default")
      (node (ref "C883") (pin "2") (pinfunction "2_2") (pintype "passive"))
      (node (ref "J18") (pin "1") (pinfunction "1_1") (pintype "bidirectional"))
    )
    (net (code "187") (name "/Tx0_N") (class "Default")
      (node (ref "C222") (pin "1") (pinfunction "1_1") (pintype "passive"))
      (node (ref "C885") (pin "1") (pinfunction "1_1") (pintype "passive"))
    )
    (net (code "188") (name "/Tx0_P") (class "Default")
      (node (ref "C221") (pin "1") (pinfunction "1_1") (pintype "passive"))
      (node (ref "C886") (pin "1") (pinfunction "1_1") (pintype "passive"))
    )
    (net (code "189") (name "/Tx1_N") (class "Default")
      (node (ref "C227") (pin "1") (pinfunction "1_1") (pintype "passive"))
    )
    (net (code "190") (name "/Tx1_P") (class "Default")
      (node (ref "C225") (pin "1") (pinfunction "1_1") (pintype "passive"))
    )
    (net (code "191") (name "/Tx2_N") (class "Default")
      (node (ref "C514") (pin "2") (pinfunction "2_2") (pintype "passive"))
    )
    (net (code "192") (name "/Tx2_P") (class "Default")
      (node (ref "C575") (pin "2") (pinfunction "2_2") (pintype "passive"))
    )
    (net (code "193") (name "/Tx3_N") (class "Default")
      (node (ref "C752") (pin "2") (pinfunction "2_2") (pintype "passive"))
    )
    (net (code "194") (name "/Tx3_P") (class "Default")
      (node (ref "C753") (pin "2") (pinfunction "2_2") (pintype "passive"))
    )
    (net (code "195") (name "/Tx4_N") (class "Default")
      (node (ref "C335") (pin "1") (pinfunction "1_1") (pintype "passive"))
    )
    (net (code "196") (name "/Tx4_P") (class "Default")
      (node (ref "C334") (pin "1") (pinfunction "1_1") (pintype "passive"))
    )
    (net (code "197") (name "/Tx5_N") (class "Default")
      (node (ref "C339") (pin "1") (pinfunction "1_1") (pintype "passive"))
    )
    (net (code "198") (name "/Tx5_P") (class "Default")
      (node (ref "C338") (pin "1") (pinfunction "1_1") (pintype "passive"))
    )
    (net (code "199") (name "/Tx6_N") (class "Default")
      (node (ref "C347") (pin "1") (pinfunction "1_1") (pintype "passive"))
    )
    (net (code "200") (name "/Tx6_P") (class "Default")
      (node (ref "C346") (pin "1") (pinfunction "1_1") (pintype "passive"))
    )
    (net (code "201") (name "/Tx7_N") (class "Default")
      (node (ref "C343") (pin "1") (pinfunction "1_1") (pintype "passive"))
    )
    (net (code "202") (name "/Tx7_P") (class "Default")
      (node (ref "C342") (pin "1") (pinfunction "1_1") (pintype "passive"))
    )
    (net (code "203") (name "/Tx8_N") (class "Default")
      (node (ref "C319") (pin "1") (pinfunction "1_1") (pintype "passive"))
    )
    (net (code "204") (name "/Tx8_P") (class "Default")
      (node (ref "C318") (pin "1") (pinfunction "1_1") (pintype "passive"))
    )
    (net (code "205") (name "/Tx9_N") (class "Default")
      (node (ref "C323") (pin "1") (pinfunction "1_1") (pintype "passive"))
    )
    (net (code "206") (name "/Tx9_P") (class "Default")
      (node (ref "C322") (pin "1") (pinfunction "1_1") (pintype "passive"))
    )
    (net (code "207") (name "/Tx10_N") (class "Default")
      (node (ref "C327") (pin "1") (pinfunction "1_1") (pintype "passive"))
    )
    (net (code "208") (name "/Tx10_P") (class "Default")
      (node (ref "C326") (pin "1") (pinfunction "1_1") (pintype "passive"))
    )
    (net (code "209") (name "/Tx11_N") (class "Default")
      (node (ref "C331") (pin "1") (pinfunction "1_1") (pintype "passive"))
    )
    (net (code "210") (name "/Tx11_P") (class "Default")
      (node (ref "C330") (pin "1") (pinfunction "1_1") (pintype "passive"))
    )
    (net (code "211") (name "/Tx12_N") (class "Default")
      (node (ref "C823") (pin "1") (pinfunction "1_1") (pintype "passive"))
    )
    (net (code "212") (name "/Tx12_P") (class "Default")
      (node (ref "C822") (pin "1") (pinfunction "1_1") (pintype "passive"))
    )
    (net (code "213") (name "/Tx13_N") (class "Default")
      (node (ref "C831") (pin "1") (pinfunction "1_1") (pintype "passive"))
    )
    (net (code "214") (name "/Tx13_P") (class "Default")
      (node (ref "C830") (pin "1") (pinfunction "1_1") (pintype "passive"))
    )
    (net (code "215") (name "/Tx14_N") (class "Default")
      (node (ref "C827") (pin "1") (pinfunction "1_1") (pintype "passive"))
    )
    (net (code "216") (name "/Tx14_P") (class "Default")
      (node (ref "C826") (pin "1") (pinfunction "1_1") (pintype "passive"))
    )
    (net (code "217") (name "/Tx15_N") (class "Default")
      (node (ref "C835") (pin "1") (pinfunction "1_1") (pintype "passive"))
    )
    (net (code "218") (name "/Tx15_P") (class "Default")
      (node (ref "C834") (pin "1") (pinfunction "1_1") (pintype "passive"))
    )
    (net (code "219") (name "/Tx113_0_N") (class "Default")
      (node (ref "C319") (pin "2") (pinfunction "2_2") (pintype "passive"))
      (node (ref "C752") (pin "1") (pinfunction "1_1") (pintype "passive"))
      (node (ref "IC2") (pin "AP17") (pinfunction "MGTPTXN0_113_AP17") (pintype "output"))
    )
    (net (code "220") (name "/Tx113_0_P") (class "Default")
      (node (ref "C318") (pin "2") (pinfunction "2_2") (pintype "passive"))
      (node (ref "C753") (pin "1") (pinfunction "1_1") (pintype "passive"))
      (node (ref "IC2") (pin "AN17") (pinfunction "MGTPTXP0_113_AN17") (pintype "output"))
    )
    (net (code "221") (name "/Tx113_1_N") (class "Default")
      (node (ref "C323") (pin "2") (pinfunction "2_2") (pintype "passive"))
      (node (ref "C514") (pin "1") (pinfunction "1_1") (pintype "passive"))
      (node (ref "IC2") (pin "AP15") (pinfunction "MGTPTXN1_113_AP15") (pintype "output"))
    )
    (net (code "222") (name "/Tx113_1_P") (class "Default")
      (node (ref "C322") (pin "2") (pinfunction "2_2") (pintype "passive"))
      (node (ref "C575") (pin "1") (pinfunction "1_1") (pintype "passive"))
      (node (ref "IC2") (pin "AN15") (pinfunction "MGTPTXP1_113_AN15") (pintype "output"))
    )
    (net (code "223") (name "/Tx113_2_N") (class "Default")
      (node (ref "C227") (pin "2") (pinfunction "2_2") (pintype "passive"))
      (node (ref "C327") (pin "2") (pinfunction "2_2") (pintype "passive"))
      (node (ref "IC2") (pin "AM14") (pinfunction "MGTPTXN2_113_AM14") (pintype "output"))
    )
    (net (code "224") (name "/Tx113_2_P") (class "Default")
      (node (ref "C225") (pin "2") (pinfunction "2_2") (pintype "passive"))
      (node (ref "C326") (pin "2") (pinfunction "2_2") (pintype "passive"))
      (node (ref "IC2") (pin "AL14") (pinfunction "MGTPTXP2_113_AL14") (pintype "output"))
    )
    (net (code "225") (name "/Tx113_3_N") (class "Default")
      (node (ref "C222") (pin "2") (pinfunction "2_2") (pintype "passive"))
      (node (ref "C331") (pin "2") (pinfunction "2_2") (pintype "passive"))
      (node (ref "IC2") (pin "AP13") (pinfunction "MGTPTXN3_113_AP13") (pintype "output"))
    )
    (net (code "226") (name "/Tx113_3_P") (class "Default")
      (node (ref "C221") (pin "2") (pinfunction "2_2") (pintype "passive"))
      (node (ref "C330") (pin "2") (pinfunction "2_2") (pintype "passive"))
      (node (ref "IC2") (pin "AN13") (pinfunction "MGTPTXP3_113_AN13") (pintype "output"))
    )
    (net (code "227") (name "/Tx116_0_N") (class "Default")
      (node (ref "C195") (pin "2") (pinfunction "2_2") (pintype "passive"))
      (node (ref "C778") (pin "2") (pinfunction "2_2") (pintype "passive"))
      (node (ref "IC2") (pin "A13") (pinfunction "MGTPTXN0_116_A13") (pintype "output"))
    )
    (net (code "228") (name "/Tx116_0_P") (class "Default")
      (node (ref "C194") (pin "2") (pinfunction "2_2") (pintype "passive"))
      (node (ref "C777") (pin "2") (pinfunction "2_2") (pintype "passive"))
      (node (ref "IC2") (pin "B13") (pinfunction "MGTPTXP0_116_B13") (pintype "output"))
    )
    (net (code "229") (name "/Tx116_1_N") (class "Default")
      (node (ref "C191") (pin "2") (pinfunction "2_2") (pintype "passive"))
      (node (ref "C782") (pin "2") (pinfunction "2_2") (pintype "passive"))
      (node (ref "IC2") (pin "C14") (pinfunction "MGTPTXN1_116_C14") (pintype "output"))
    )
    (net (code "230") (name "/Tx116_1_P") (class "Default")
      (node (ref "C190") (pin "2") (pinfunction "2_2") (pintype "passive"))
      (node (ref "C781") (pin "2") (pinfunction "2_2") (pintype "passive"))
      (node (ref "IC2") (pin "D14") (pinfunction "MGTPTXP1_116_D14") (pintype "output"))
    )
    (net (code "231") (name "/Tx116_2_N") (class "Default")
      (node (ref "C185") (pin "2") (pinfunction "2_2") (pintype "passive"))
      (node (ref "C786") (pin "2") (pinfunction "2_2") (pintype "passive"))
      (node (ref "IC2") (pin "A15") (pinfunction "MGTPTXN2_116_A15") (pintype "output"))
    )
    (net (code "232") (name "/Tx116_2_P") (class "Default")
      (node (ref "C184") (pin "2") (pinfunction "2_2") (pintype "passive"))
      (node (ref "C785") (pin "2") (pinfunction "2_2") (pintype "passive"))
      (node (ref "IC2") (pin "B15") (pinfunction "MGTPTXP2_116_B15") (pintype "output"))
    )
    (net (code "233") (name "/Tx116_3_N") (class "Default")
      (node (ref "C179") (pin "2") (pinfunction "2_2") (pintype "passive"))
      (node (ref "C790") (pin "2") (pinfunction "2_2") (pintype "passive"))
      (node (ref "IC2") (pin "A17") (pinfunction "MGTPTXN3_116_A17") (pintype "output"))
    )
    (net (code "234") (name "/Tx116_3_P") (class "Default")
      (node (ref "C178") (pin "2") (pinfunction "2_2") (pintype "passive"))
      (node (ref "C789") (pin "2") (pinfunction "2_2") (pintype "passive"))
      (node (ref "IC2") (pin "B17") (pinfunction "MGTPTXP3_116_B17") (pintype "output"))
    )
    (net (code "235") (name "/Tx213_0_N") (class "Default")
      (node (ref "C199") (pin "2") (pinfunction "2_2") (pintype "passive"))
      (node (ref "C796") (pin "2") (pinfunction "2_2") (pintype "passive"))
      (node (ref "C823") (pin "2") (pinfunction "2_2") (pintype "passive"))
      (node (ref "IC2") (pin "AP19") (pinfunction "MGTPTXN0_213_AP19") (pintype "output"))
    )
    (net (code "236") (name "/Tx213_0_P") (class "Default")
      (node (ref "C198") (pin "2") (pinfunction "2_2") (pintype "passive"))
      (node (ref "C795") (pin "2") (pinfunction "2_2") (pintype "passive"))
      (node (ref "C822") (pin "2") (pinfunction "2_2") (pintype "passive"))
      (node (ref "IC2") (pin "AN19") (pinfunction "MGTPTXP0_213_AN19") (pintype "output"))
    )
    (net (code "237") (name "/Tx213_1_N") (class "Default")
      (node (ref "C205") (pin "2") (pinfunction "2_2") (pintype "passive"))
      (node (ref "C802") (pin "2") (pinfunction "2_2") (pintype "passive"))
      (node (ref "C827") (pin "2") (pinfunction "2_2") (pintype "passive"))
      (node (ref "IC2") (pin "AP21") (pinfunction "MGTPTXN1_213_AP21") (pintype "output"))
    )
    (net (code "238") (name "/Tx213_1_P") (class "Default")
      (node (ref "C204") (pin "2") (pinfunction "2_2") (pintype "passive"))
      (node (ref "C801") (pin "2") (pinfunction "2_2") (pintype "passive"))
      (node (ref "C826") (pin "2") (pinfunction "2_2") (pintype "passive"))
      (node (ref "IC2") (pin "AN21") (pinfunction "MGTPTXP1_213_AN21") (pintype "output"))
    )
    (net (code "239") (name "/Tx213_2_N") (class "Default")
      (node (ref "C629") (pin "2") (pinfunction "2_2") (pintype "passive"))
      (node (ref "C806") (pin "2") (pinfunction "2_2") (pintype "passive"))
      (node (ref "C831") (pin "2") (pinfunction "2_2") (pintype "passive"))
      (node (ref "IC2") (pin "AM22") (pinfunction "MGTPTXN2_213_AM22") (pintype "output"))
    )
    (net (code "240") (name "/Tx213_2_P") (class "Default")
      (node (ref "C627") (pin "2") (pinfunction "2_2") (pintype "passive"))
      (node (ref "C805") (pin "2") (pinfunction "2_2") (pintype "passive"))
      (node (ref "C830") (pin "2") (pinfunction "2_2") (pintype "passive"))
      (node (ref "IC2") (pin "AL22") (pinfunction "MGTPTXP2_213_AL22") (pintype "output"))
    )
    (net (code "241") (name "/Tx213_3_N") (class "Default")
      (node (ref "C628") (pin "2") (pinfunction "2_2") (pintype "passive"))
      (node (ref "C810") (pin "2") (pinfunction "2_2") (pintype "passive"))
      (node (ref "C835") (pin "2") (pinfunction "2_2") (pintype "passive"))
      (node (ref "IC2") (pin "AP23") (pinfunction "MGTPTXN3_213_AP23") (pintype "output"))
    )
    (net (code "242") (name "/Tx213_3_P") (class "Default")
      (node (ref "C626") (pin "2") (pinfunction "2_2") (pintype "passive"))
      (node (ref "C809") (pin "2") (pinfunction "2_2") (pintype "passive"))
      (node (ref "C834") (pin "2") (pinfunction "2_2") (pintype "passive"))
      (node (ref "IC2") (pin "AN23") (pinfunction "MGTPTXP3_213_AN23") (pintype "output"))
    )
    (net (code "243") (name "/Tx216_0_N") (class "Default")
      (node (ref "C335") (pin "2") (pinfunction "2_2") (pintype "passive"))
      (node (ref "IC2") (pin "A23") (pinfunction "MGTPTXN0_216_A23") (pintype "output"))
    )
    (net (code "244") (name "/Tx216_0_P") (class "Default")
      (node (ref "C334") (pin "2") (pinfunction "2_2") (pintype "passive"))
      (node (ref "IC2") (pin "B23") (pinfunction "MGTPTXP0_216_B23") (pintype "output"))
    )
    (net (code "245") (name "/Tx216_1_N") (class "Default")
      (node (ref "C339") (pin "2") (pinfunction "2_2") (pintype "passive"))
      (node (ref "IC2") (pin "C22") (pinfunction "MGTPTXN1_216_C22") (pintype "output"))
    )
    (net (code "246") (name "/Tx216_1_P") (class "Default")
      (node (ref "C338") (pin "2") (pinfunction "2_2") (pintype "passive"))
      (node (ref "IC2") (pin "D22") (pinfunction "MGTPTXP1_216_D22") (pintype "output"))
    )
    (net (code "247") (name "/Tx216_2_N") (class "Default")
      (node (ref "C347") (pin "2") (pinfunction "2_2") (pintype "passive"))
      (node (ref "IC2") (pin "A21") (pinfunction "MGTPTXN2_216_A21") (pintype "output"))
    )
    (net (code "248") (name "/Tx216_2_P") (class "Default")
      (node (ref "C346") (pin "2") (pinfunction "2_2") (pintype "passive"))
      (node (ref "IC2") (pin "B21") (pinfunction "MGTPTXP2_216_B21") (pintype "output"))
    )
    (net (code "249") (name "/Tx216_3_N") (class "Default")
      (node (ref "C343") (pin "2") (pinfunction "2_2") (pintype "passive"))
      (node (ref "IC2") (pin "A19") (pinfunction "MGTPTXN3_216_A19") (pintype "output"))
    )
    (net (code "250") (name "/Tx216_3_P") (class "Default")
      (node (ref "C342") (pin "2") (pinfunction "2_2") (pintype "passive"))
      (node (ref "IC2") (pin "B19") (pinfunction "MGTPTXP3_216_B19") (pintype "output"))
    )
    (net (code "251") (name "/TxC0_N") (class "Default")
      (node (ref "C885") (pin "2") (pinfunction "2_2") (pintype "passive"))
      (node (ref "J20") (pin "1") (pinfunction "1_1") (pintype "bidirectional"))
    )
    (net (code "252") (name "/TxC0_P") (class "Default")
      (node (ref "C886") (pin "2") (pinfunction "2_2") (pintype "passive"))
      (node (ref "J21") (pin "1") (pinfunction "1_1") (pintype "bidirectional"))
    )
    (net (code "265") (name "GND") (class "Default")
      (node (ref "J18") (pin "2") (pinfunction "2_2") (pintype "bidirectional"))
      (node (ref "J19") (pin "2") (pinfunction "2_2") (pintype "bidirectional"))
      (node (ref "J20") (pin "2") (pinfunction "2_2") (pintype "bidirectional"))
      (node (ref "J21") (pin "2") (pinfunction "2_2") (pintype "bidirectional"))
    )
    (net (code "266") (name "MGTAVTT_G10") (class "Default")
      (node (ref "R239") (pin "1") (pinfunction "1_1") (pintype "passive"))
    )
    (net (code "267") (name "MGTAVTT_G11") (class "Default")
      (node (ref "R142") (pin "1") (pinfunction "1_1") (pintype "passive"))
    )
  )
)
